# Lamp_Logic_Board_Combo.net
KiCad netlist of a schematic drawn in EAGLE
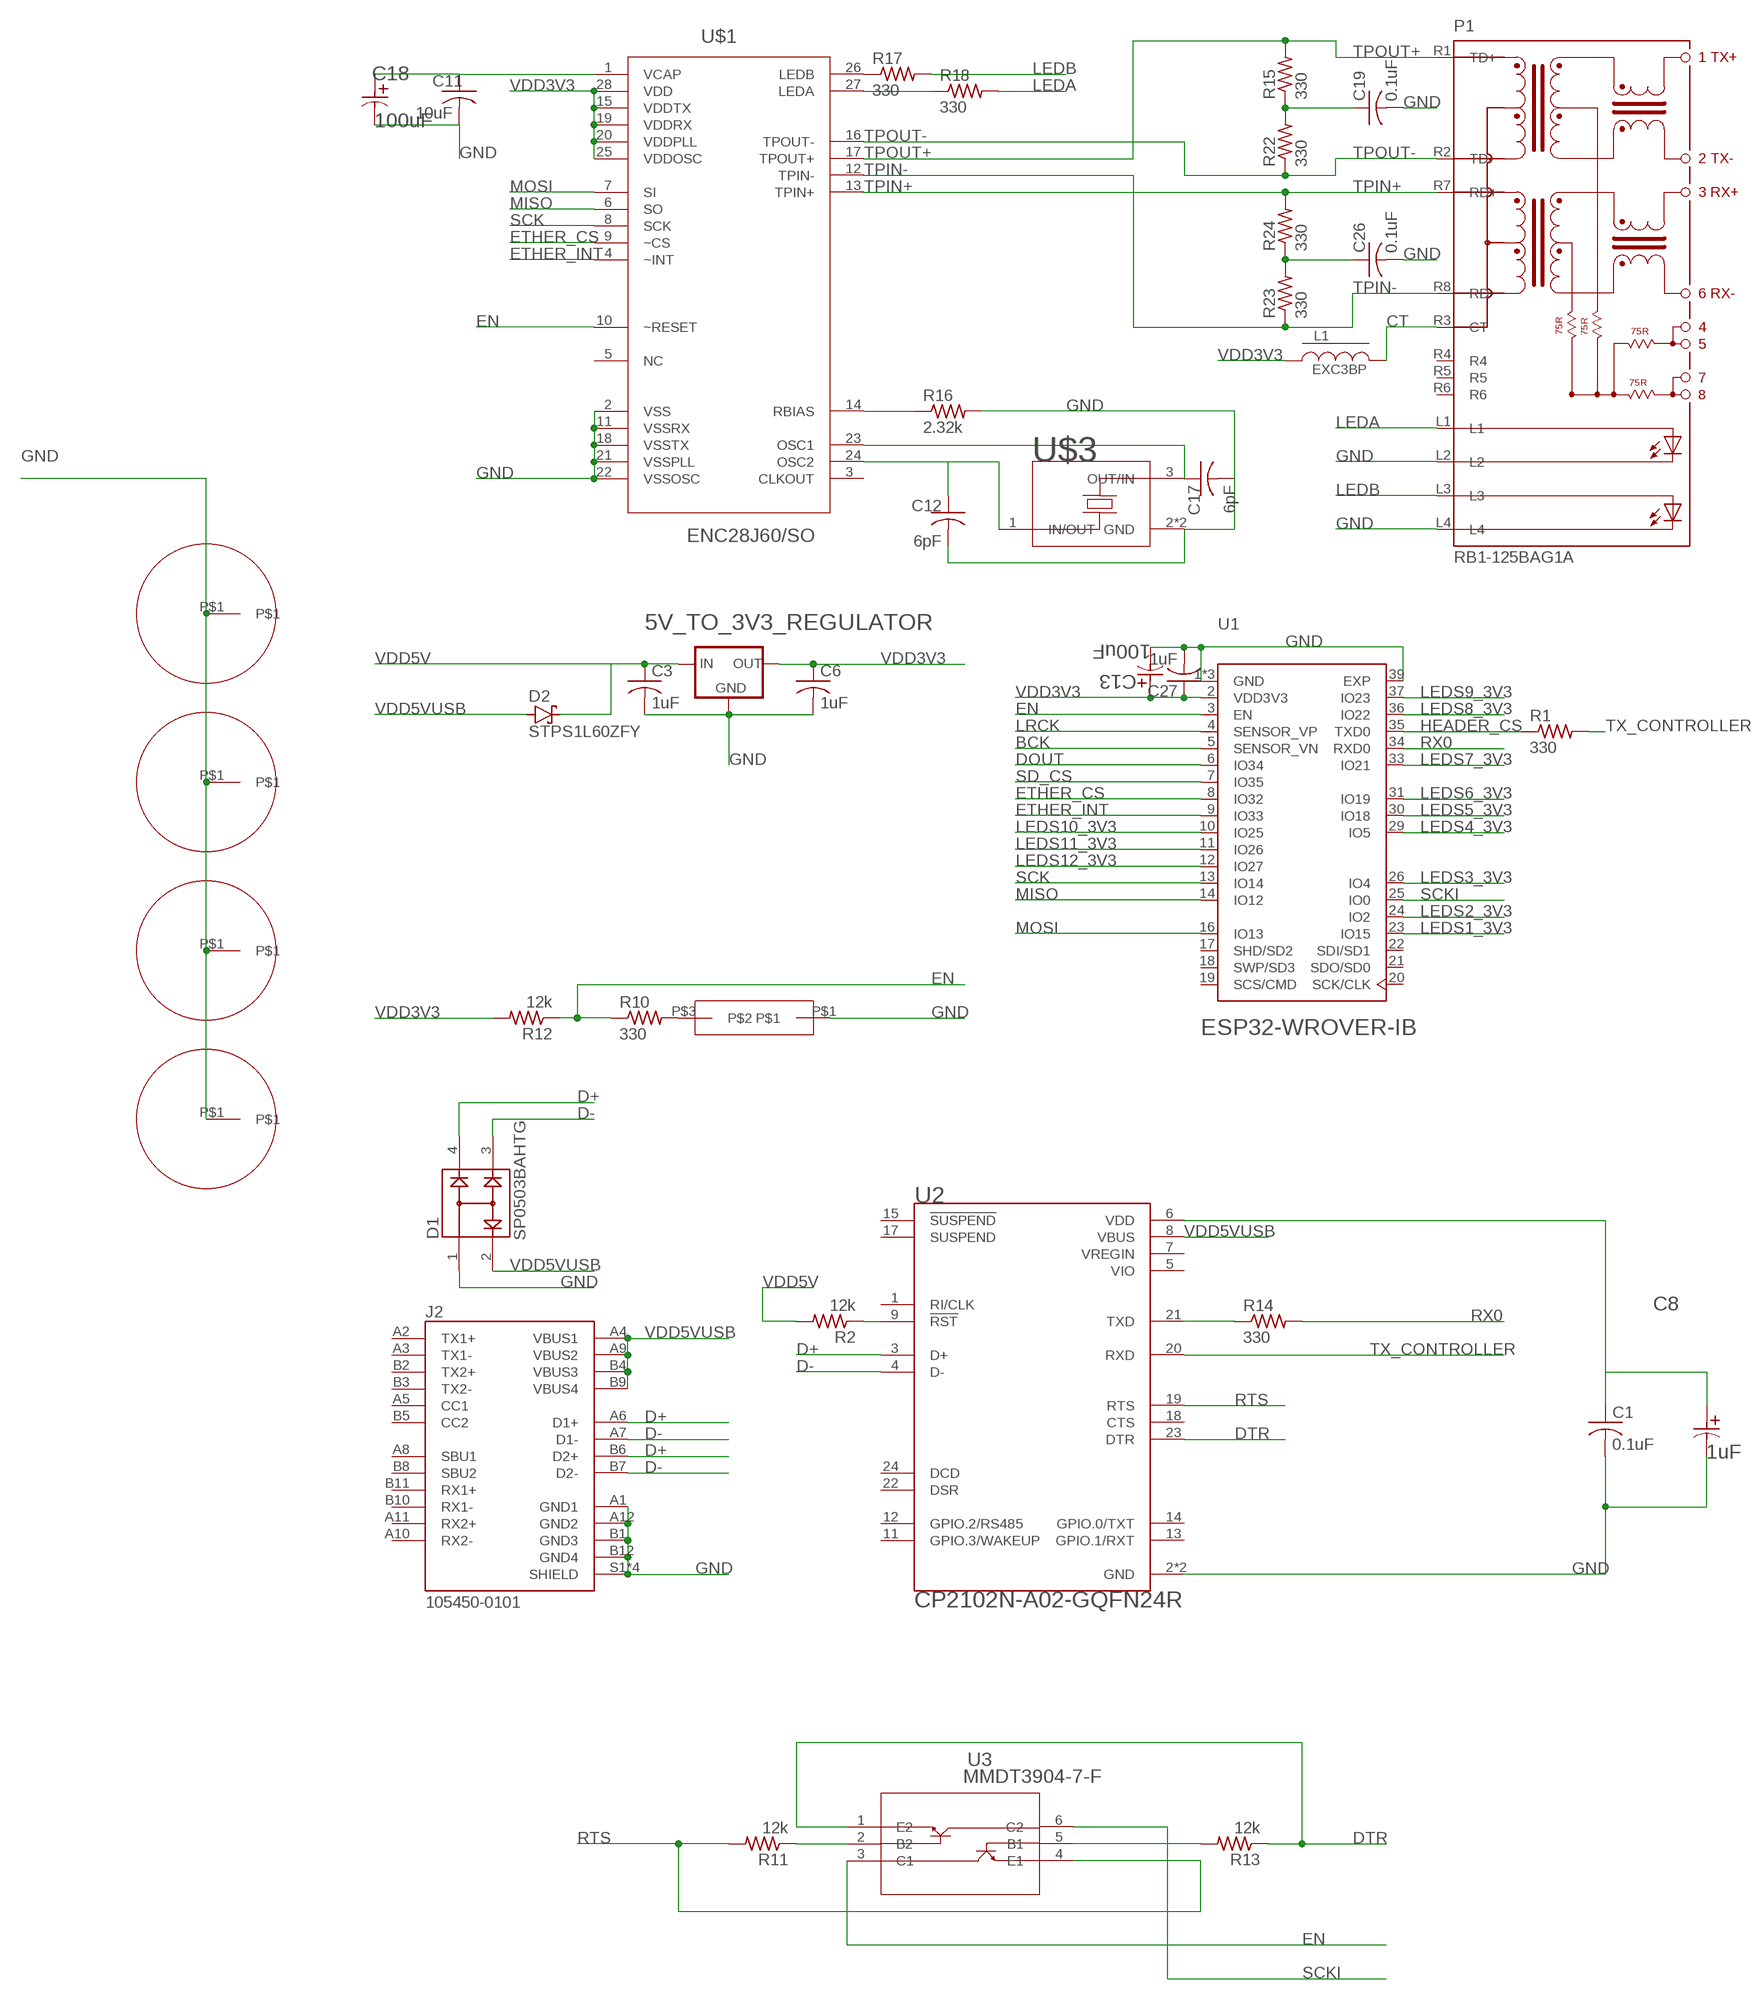
[diagram p0: schematic, sheet 1, part 1 of 2]
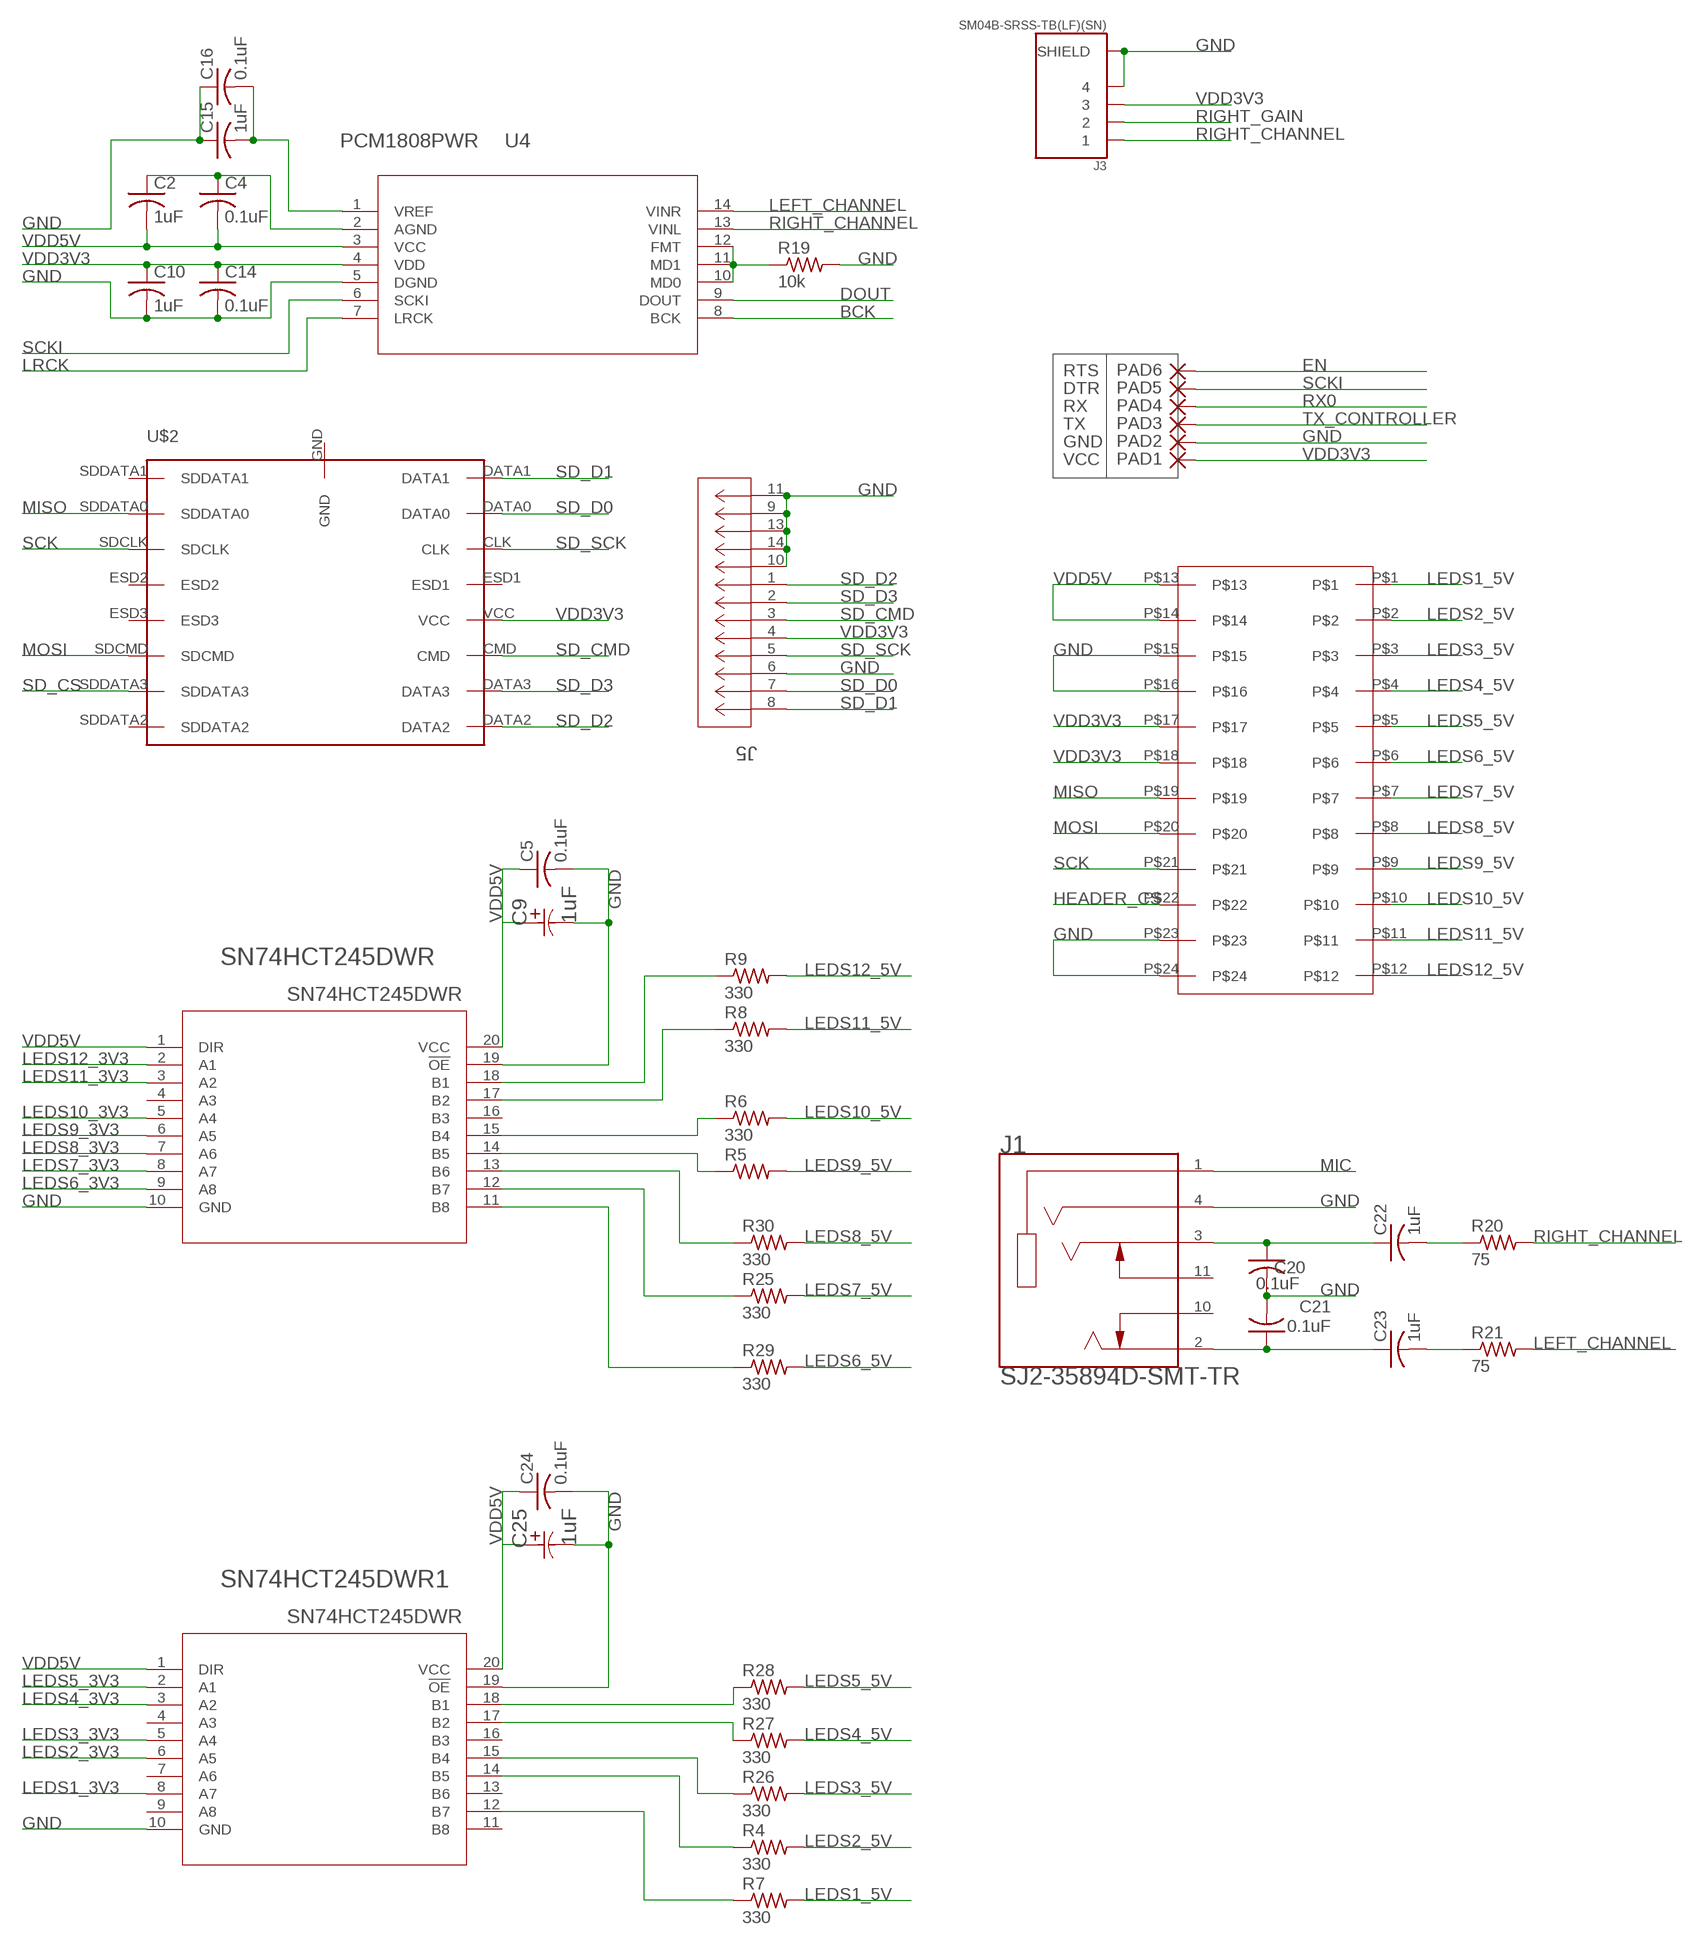
[diagram p1: schematic, sheet 1, part 2 of 2]
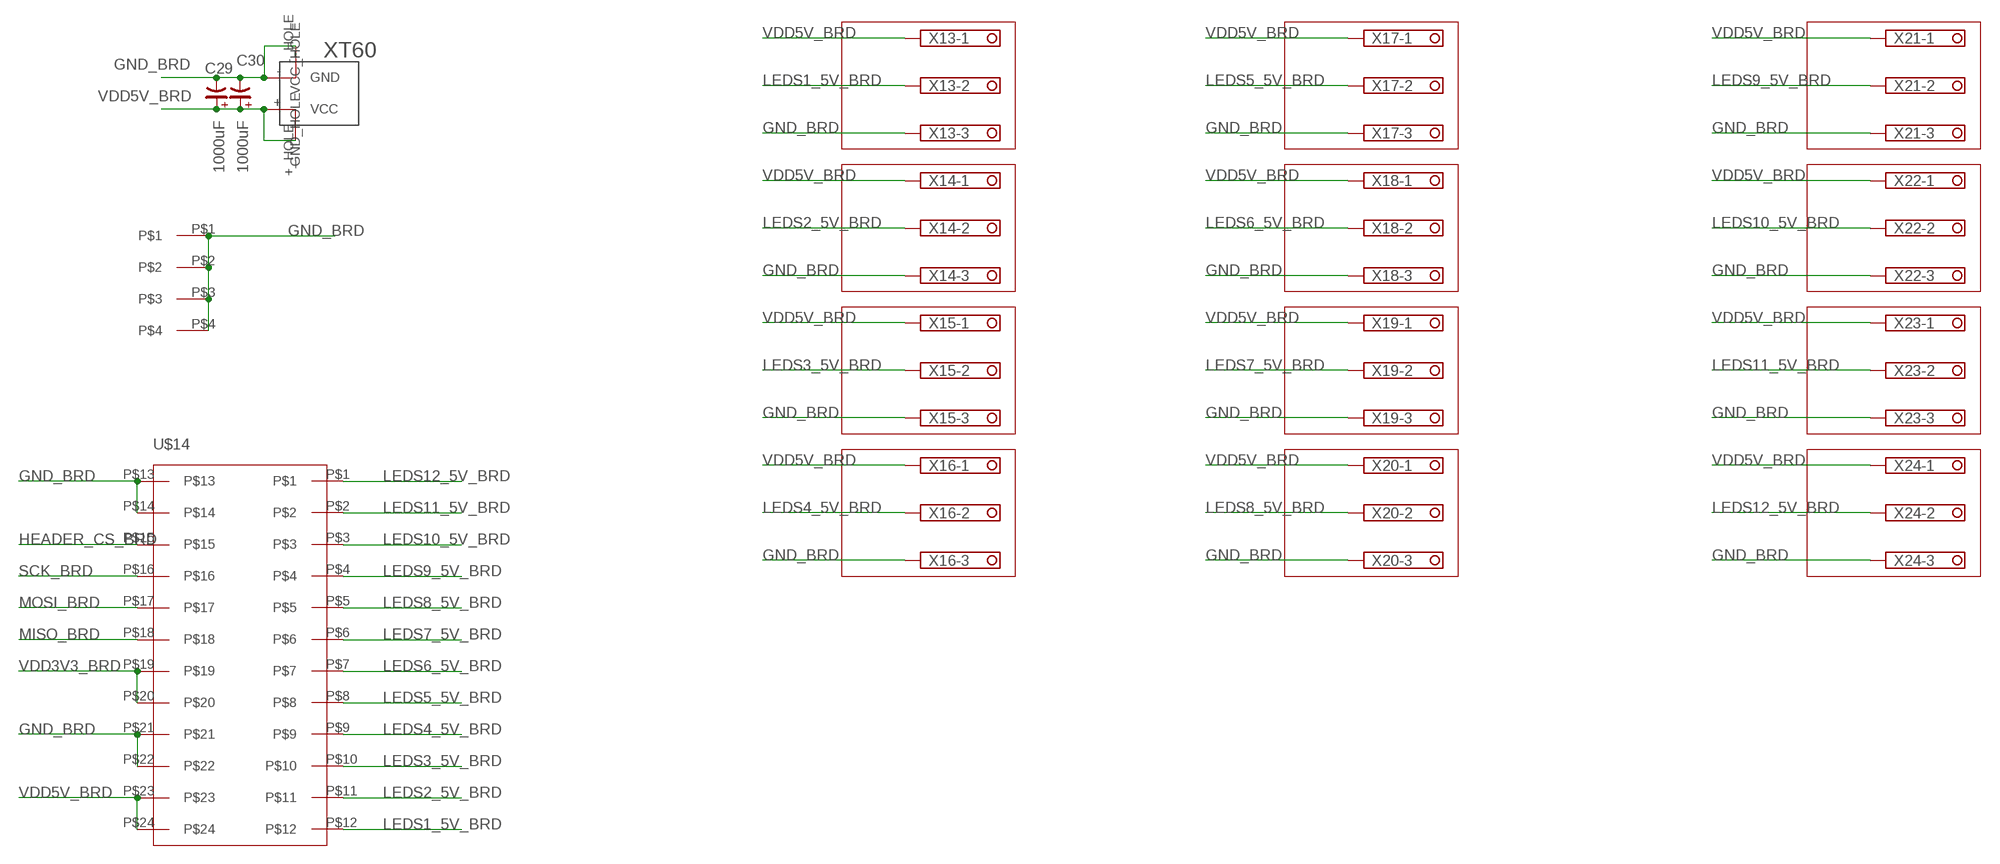
[diagram p2: schematic, sheet 2]

(export (version "E")
  (design (tool "Eeschema 10.0.6"))
  (components
    (comp (ref "5V_TO_3V3_REGULATOR")
      (value "LM1117MP-1.8")
      (footprint "eagle-import:SOT223")
      (fields (field (name "MF") "Texas Instruments"))
      (libsource (lib "eagle-import") (part "LM1117?-MP1.8"))
    )
    (comp (ref "C1")
      (value "0.1uF")
      (footprint "eagle-import:C0402")
      (libsource (lib "eagle-import") (part "resistor_348_C-USC0402"))
    )
    (comp (ref "C2")
      (value "1uF")
      (footprint "eagle-import:C0402")
      (libsource (lib "eagle-import") (part "resistor_348_C-USC0402"))
    )
    (comp (ref "C3")
      (value "1uF")
      (footprint "eagle-import:C0402")
      (libsource (lib "eagle-import") (part "resistor_348_C-USC0402"))
    )
    (comp (ref "C4")
      (value "0.1uF")
      (footprint "eagle-import:C0402")
      (libsource (lib "eagle-import") (part "resistor_348_C-USC0402"))
    )
    (comp (ref "C5")
      (value "0.1uF")
      (footprint "eagle-import:C0402")
      (libsource (lib "eagle-import") (part "C-USC0402"))
    )
    (comp (ref "C6")
      (value "1uF")
      (footprint "eagle-import:C0402")
      (libsource (lib "eagle-import") (part "resistor_348_C-USC0402"))
    )
    (comp (ref "C8")
      (value "1uF")
      (footprint "eagle-import:CAP_EEFC_B")
      (fields (field (name "MANUFACTURER_PART_NUMBER") "EEEFC1V1R0R"))
      (libsource (lib "eagle-import") (part "EEEFC1V1R0R"))
    )
    (comp (ref "C9")
      (value "1uF")
      (footprint "eagle-import:CAP_EEFC_B")
      (fields (field (name "MANUFACTURER_PART_NUMBER") "EEEFC1V1R0R"))
      (libsource (lib "eagle-import") (part "EEEFC1V1R0R"))
    )
    (comp (ref "C10")
      (value "1uF")
      (footprint "eagle-import:C0402")
      (libsource (lib "eagle-import") (part "resistor_348_C-USC0402"))
    )
    (comp (ref "C11")
      (value "10uF")
      (footprint "eagle-import:C0402")
      (libsource (lib "eagle-import") (part "resistor_348_C-USC0402"))
    )
    (comp (ref "C12")
      (value "6pF")
      (footprint "eagle-import:C0402")
      (libsource (lib "eagle-import") (part "resistor_348_C-USC0402"))
    )
    (comp (ref "C13")
      (value "100uF")
      (footprint "eagle-import:CAP_EEFC_B")
      (fields (field (name "MANUFACTURER_PART_NUMBER") "EEEFC1V1R0R"))
      (libsource (lib "eagle-import") (part "EEEFC1V1R0R"))
    )
    (comp (ref "C14")
      (value "0.1uF")
      (footprint "eagle-import:C0402")
      (libsource (lib "eagle-import") (part "resistor_348_C-USC0402"))
    )
    (comp (ref "C15")
      (value "1uF")
      (footprint "eagle-import:C0402")
      (libsource (lib "eagle-import") (part "resistor_348_C-USC0402"))
    )
    (comp (ref "C16")
      (value "0.1uF")
      (footprint "eagle-import:C0402")
      (libsource (lib "eagle-import") (part "resistor_348_C-USC0402"))
    )
    (comp (ref "C17")
      (value "6pF")
      (footprint "eagle-import:C0402")
      (libsource (lib "eagle-import") (part "resistor_348_C-USC0402"))
    )
    (comp (ref "C18")
      (value "100uF")
      (footprint "eagle-import:CAP_EEFC_B")
      (fields (field (name "MANUFACTURER_PART_NUMBER") "EEEFC1V1R0R"))
      (libsource (lib "eagle-import") (part "EEEFC1V1R0R"))
    )
    (comp (ref "C19")
      (value "0.1uF")
      (footprint "eagle-import:C0402")
      (libsource (lib "eagle-import") (part "resistor_348_C-USC0402"))
    )
    (comp (ref "C20")
      (value "0.1uF")
      (footprint "eagle-import:C0402")
      (libsource (lib "eagle-import") (part "C-USC0402"))
    )
    (comp (ref "C21")
      (value "0.1uF")
      (footprint "eagle-import:C0402")
      (libsource (lib "eagle-import") (part "C-USC0402"))
    )
    (comp (ref "C22")
      (value "1uF")
      (footprint "eagle-import:C0402")
      (libsource (lib "eagle-import") (part "resistor_348_C-USC0402"))
    )
    (comp (ref "C23")
      (value "1uF")
      (footprint "eagle-import:C0402")
      (libsource (lib "eagle-import") (part "resistor_348_C-USC0402"))
    )
    (comp (ref "C24")
      (value "0.1uF")
      (footprint "eagle-import:C0402")
      (libsource (lib "eagle-import") (part "C-USC0402"))
    )
    (comp (ref "C25")
      (value "1uF")
      (footprint "eagle-import:CAP_EEFC_B")
      (fields (field (name "MANUFACTURER_PART_NUMBER") "EEEFC1V1R0R"))
      (libsource (lib "eagle-import") (part "EEEFC1V1R0R"))
    )
    (comp (ref "C26")
      (value "0.1uF")
      (footprint "eagle-import:C0402")
      (libsource (lib "eagle-import") (part "resistor_348_C-USC0402"))
    )
    (comp (ref "C27")
      (value "1uF")
      (footprint "eagle-import:C0402")
      (libsource (lib "eagle-import") (part "resistor_348_C-USC0402"))
    )
    (comp (ref "D1")
      (value "SP0503BAHTG")
      (footprint "eagle-import:SOT143")
      (fields (field (name "DIGI-KEY_PART_NUMBER") "F2715CT-ND") (field (name "MF") "Littelfuse Inc."))
      (libsource (lib "eagle-import") (part "SP0503BAHTG"))
    )
    (comp (ref "D2")
      (value "STPS1L60ZFY")
      (footprint "eagle-import:SOD-123")
      (fields
        (field (name "DIGIKEY_PART_NUMBER") "MBR0520LT1GOSTR-ND")
        (field (name "MANUFACTURER") "ON Semiconductor")
        (field (name "MPN") "MBR0520LT1G")
        (field (name "CREATED_BY") "PCBLayout.com")
      )
      (libsource (lib "eagle-import") (part "MBR0520LT1G"))
    )
    (comp (ref "J1")
      (value "SJ2-35894D-SMT-TR")
      (footprint "eagle-import:CUI_SJ2-35894D-SMT-TR")
      (fields (field (name "DIGI-KEY_PART_NUMBER") "CP-SJ2-35894D-SMT-CT-ND") (field (name "MF") "CUI Inc."))
      (libsource (lib "eagle-import") (part "SJ2-35894D-SMT-TR"))
    )
    (comp (ref "J2")
      (value "105450-0101")
      (footprint "eagle-import:MOLEX_105450-0101")
      (fields
        (field (name "DIGI-KEY_PART_NUMBER") "WM12856CT-ND")
        (field (name "MF") "Molex")
        (field (name "MP") "1054500101")
      )
      (libsource (lib "eagle-import") (part "105450-0101"))
    )
    (comp (ref "J3")
      (value "SM04B-SRSS-TB(LF)(SN)")
      (footprint "eagle-import:JST_SM04B-SRSS-TB(LF)(SN)")
      (fields (field (name "MF") "JST Sales") (field (name "MP") "SM04B-SRSS-TB_LF__SN_"))
      (libsource (lib "eagle-import") (part "SM04B-SRSS-TB(LF)(SN)"))
    )
    (comp (ref "J5")
      (value "LLC")
      (footprint "eagle-import:CON00218_8")
      (libsource (lib "eagle-import") (part "LLC"))
    )
    (comp (ref "L1")
      (value "EXC3BP")
      (footprint "eagle-import:L0603")
      (libsource (lib "eagle-import") (part "EXC3BP"))
    )
    (comp (ref "P1")
      (value "RB1-125BAG1A")
      (footprint "eagle-import:WIZNET_RB1-125BAG1A")
      (fields (field (name "MF") "WIZnet"))
      (libsource (lib "eagle-import") (part "RB1-125BAG1A"))
    )
    (comp (ref "PAD1")
      (value "VCC")
      (footprint "eagle-import:SMD1,27-2,54")
      (libsource (lib "eagle-import") (part "WIREPADSMD1,27-254"))
    )
    (comp (ref "PAD2")
      (value "GND")
      (footprint "eagle-import:SMD1,27-2,54")
      (libsource (lib "eagle-import") (part "WIREPADSMD1,27-254"))
    )
    (comp (ref "PAD3")
      (value "TX")
      (footprint "eagle-import:SMD1,27-2,54")
      (libsource (lib "eagle-import") (part "WIREPADSMD1,27-254"))
    )
    (comp (ref "PAD4")
      (value "RX")
      (footprint "eagle-import:SMD1,27-2,54")
      (libsource (lib "eagle-import") (part "WIREPADSMD1,27-254"))
    )
    (comp (ref "PAD5")
      (value "DTR")
      (footprint "eagle-import:SMD1,27-2,54")
      (libsource (lib "eagle-import") (part "WIREPADSMD1,27-254"))
    )
    (comp (ref "PAD6")
      (value "RTS")
      (footprint "eagle-import:SMD1,27-2,54")
      (libsource (lib "eagle-import") (part "WIREPADSMD1,27-254"))
    )
    (comp (ref "R1")
      (value "330")
      (footprint "eagle-import:RES_0603")
      (fields
        (field (name "DIGIKEY_PART_NUMBER") "311-0.0GRTR-ND")
        (field (name "MANUFACTURER") "Yageo")
        (field (name "MPN") "RC0603JR-070RL")
        (field (name "CREATED_BY") "PCBLayout.com")
      )
      (libsource (lib "eagle-import") (part "RC0603JR-070RL"))
    )
    (comp (ref "R2")
      (value "12k")
      (footprint "eagle-import:RES_0603")
      (fields
        (field (name "DIGIKEY_PART_NUMBER") "311-0.0GRTR-ND")
        (field (name "MANUFACTURER") "Yageo")
        (field (name "MPN") "RC0603JR-070RL")
        (field (name "CREATED_BY") "PCBLayout.com")
      )
      (libsource (lib "eagle-import") (part "RC0603JR-070RL"))
    )
    (comp (ref "R4")
      (value "330")
      (footprint "eagle-import:RES_0603")
      (fields
        (field (name "DIGIKEY_PART_NUMBER") "311-0.0GRTR-ND")
        (field (name "MANUFACTURER") "Yageo")
        (field (name "MPN") "RC0603JR-070RL")
        (field (name "CREATED_BY") "PCBLayout.com")
      )
      (libsource (lib "eagle-import") (part "RC0603JR-070RL"))
    )
    (comp (ref "R5")
      (value "330")
      (footprint "eagle-import:RES_0603")
      (fields
        (field (name "DIGIKEY_PART_NUMBER") "311-0.0GRTR-ND")
        (field (name "MANUFACTURER") "Yageo")
        (field (name "MPN") "RC0603JR-070RL")
        (field (name "CREATED_BY") "PCBLayout.com")
      )
      (libsource (lib "eagle-import") (part "RC0603JR-070RL"))
    )
    (comp (ref "R6")
      (value "330")
      (footprint "eagle-import:RES_0603")
      (fields
        (field (name "DIGIKEY_PART_NUMBER") "311-0.0GRTR-ND")
        (field (name "MANUFACTURER") "Yageo")
        (field (name "MPN") "RC0603JR-070RL")
        (field (name "CREATED_BY") "PCBLayout.com")
      )
      (libsource (lib "eagle-import") (part "RC0603JR-070RL"))
    )
    (comp (ref "R7")
      (value "330")
      (footprint "eagle-import:RES_0603")
      (fields
        (field (name "DIGIKEY_PART_NUMBER") "311-0.0GRTR-ND")
        (field (name "MANUFACTURER") "Yageo")
        (field (name "MPN") "RC0603JR-070RL")
        (field (name "CREATED_BY") "PCBLayout.com")
      )
      (libsource (lib "eagle-import") (part "RC0603JR-070RL"))
    )
    (comp (ref "R8")
      (value "330")
      (footprint "eagle-import:RES_0603")
      (fields
        (field (name "DIGIKEY_PART_NUMBER") "311-0.0GRTR-ND")
        (field (name "MANUFACTURER") "Yageo")
        (field (name "MPN") "RC0603JR-070RL")
        (field (name "CREATED_BY") "PCBLayout.com")
      )
      (libsource (lib "eagle-import") (part "RC0603JR-070RL"))
    )
    (comp (ref "R9")
      (value "330")
      (footprint "eagle-import:RES_0603")
      (fields
        (field (name "DIGIKEY_PART_NUMBER") "311-0.0GRTR-ND")
        (field (name "MANUFACTURER") "Yageo")
        (field (name "MPN") "RC0603JR-070RL")
        (field (name "CREATED_BY") "PCBLayout.com")
      )
      (libsource (lib "eagle-import") (part "RC0603JR-070RL"))
    )
    (comp (ref "R10")
      (value "330")
      (footprint "eagle-import:RES_0603")
      (fields
        (field (name "DIGIKEY_PART_NUMBER") "311-0.0GRTR-ND")
        (field (name "MANUFACTURER") "Yageo")
        (field (name "MPN") "RC0603JR-070RL")
        (field (name "CREATED_BY") "PCBLayout.com")
      )
      (libsource (lib "eagle-import") (part "RC0603JR-070RL"))
    )
    (comp (ref "R11")
      (value "12k")
      (footprint "eagle-import:RES_0603")
      (fields
        (field (name "DIGIKEY_PART_NUMBER") "311-0.0GRTR-ND")
        (field (name "MANUFACTURER") "Yageo")
        (field (name "MPN") "RC0603JR-070RL")
        (field (name "CREATED_BY") "PCBLayout.com")
      )
      (libsource (lib "eagle-import") (part "RC0603JR-070RL"))
    )
    (comp (ref "R12")
      (value "12k")
      (footprint "eagle-import:RES_0603")
      (fields
        (field (name "DIGIKEY_PART_NUMBER") "311-0.0GRTR-ND")
        (field (name "MANUFACTURER") "Yageo")
        (field (name "MPN") "RC0603JR-070RL")
        (field (name "CREATED_BY") "PCBLayout.com")
      )
      (libsource (lib "eagle-import") (part "RC0603JR-070RL"))
    )
    (comp (ref "R13")
      (value "12k")
      (footprint "eagle-import:RES_0603")
      (fields
        (field (name "DIGIKEY_PART_NUMBER") "311-0.0GRTR-ND")
        (field (name "MANUFACTURER") "Yageo")
        (field (name "MPN") "RC0603JR-070RL")
        (field (name "CREATED_BY") "PCBLayout.com")
      )
      (libsource (lib "eagle-import") (part "RC0603JR-070RL"))
    )
    (comp (ref "R14")
      (value "330")
      (footprint "eagle-import:RES_0603")
      (fields
        (field (name "DIGIKEY_PART_NUMBER") "311-0.0GRTR-ND")
        (field (name "MANUFACTURER") "Yageo")
        (field (name "MPN") "RC0603JR-070RL")
        (field (name "CREATED_BY") "PCBLayout.com")
      )
      (libsource (lib "eagle-import") (part "RC0603JR-070RL"))
    )
    (comp (ref "R15")
      (value "330")
      (footprint "eagle-import:RES_0603")
      (fields
        (field (name "DIGIKEY_PART_NUMBER") "311-0.0GRTR-ND")
        (field (name "MANUFACTURER") "Yageo")
        (field (name "MPN") "RC0603JR-070RL")
        (field (name "CREATED_BY") "PCBLayout.com")
      )
      (libsource (lib "eagle-import") (part "RC0603JR-070RL"))
    )
    (comp (ref "R16")
      (value "2.32k")
      (footprint "eagle-import:R1206")
      (libsource (lib "eagle-import") (part "R-US_R1206"))
    )
    (comp (ref "R17")
      (value "330")
      (footprint "eagle-import:RES_0603")
      (fields
        (field (name "DIGIKEY_PART_NUMBER") "311-0.0GRTR-ND")
        (field (name "MANUFACTURER") "Yageo")
        (field (name "MPN") "RC0603JR-070RL")
        (field (name "CREATED_BY") "PCBLayout.com")
      )
      (libsource (lib "eagle-import") (part "RC0603JR-070RL"))
    )
    (comp (ref "R18")
      (value "330")
      (footprint "eagle-import:RES_0603")
      (fields
        (field (name "DIGIKEY_PART_NUMBER") "311-0.0GRTR-ND")
        (field (name "MANUFACTURER") "Yageo")
        (field (name "MPN") "RC0603JR-070RL")
        (field (name "CREATED_BY") "PCBLayout.com")
      )
      (libsource (lib "eagle-import") (part "RC0603JR-070RL"))
    )
    (comp (ref "R19")
      (value "10k")
      (footprint "eagle-import:R1206")
      (libsource (lib "eagle-import") (part "R-US_R1206"))
    )
    (comp (ref "R20")
      (value "75")
      (footprint "eagle-import:R1206")
      (libsource (lib "eagle-import") (part "R-US_R1206"))
    )
    (comp (ref "R21")
      (value "75")
      (footprint "eagle-import:R1206")
      (libsource (lib "eagle-import") (part "R-US_R1206"))
    )
    (comp (ref "R22")
      (value "330")
      (footprint "eagle-import:RES_0603")
      (fields
        (field (name "DIGIKEY_PART_NUMBER") "311-0.0GRTR-ND")
        (field (name "MANUFACTURER") "Yageo")
        (field (name "MPN") "RC0603JR-070RL")
        (field (name "CREATED_BY") "PCBLayout.com")
      )
      (libsource (lib "eagle-import") (part "RC0603JR-070RL"))
    )
    (comp (ref "R23")
      (value "330")
      (footprint "eagle-import:RES_0603")
      (fields
        (field (name "DIGIKEY_PART_NUMBER") "311-0.0GRTR-ND")
        (field (name "MANUFACTURER") "Yageo")
        (field (name "MPN") "RC0603JR-070RL")
        (field (name "CREATED_BY") "PCBLayout.com")
      )
      (libsource (lib "eagle-import") (part "RC0603JR-070RL"))
    )
    (comp (ref "R24")
      (value "330")
      (footprint "eagle-import:RES_0603")
      (fields
        (field (name "DIGIKEY_PART_NUMBER") "311-0.0GRTR-ND")
        (field (name "MANUFACTURER") "Yageo")
        (field (name "MPN") "RC0603JR-070RL")
        (field (name "CREATED_BY") "PCBLayout.com")
      )
      (libsource (lib "eagle-import") (part "RC0603JR-070RL"))
    )
    (comp (ref "R25")
      (value "330")
      (footprint "eagle-import:RES_0603")
      (fields
        (field (name "DIGIKEY_PART_NUMBER") "311-0.0GRTR-ND")
        (field (name "MANUFACTURER") "Yageo")
        (field (name "MPN") "RC0603JR-070RL")
        (field (name "CREATED_BY") "PCBLayout.com")
      )
      (libsource (lib "eagle-import") (part "RC0603JR-070RL"))
    )
    (comp (ref "R26")
      (value "330")
      (footprint "eagle-import:RES_0603")
      (fields
        (field (name "DIGIKEY_PART_NUMBER") "311-0.0GRTR-ND")
        (field (name "MANUFACTURER") "Yageo")
        (field (name "MPN") "RC0603JR-070RL")
        (field (name "CREATED_BY") "PCBLayout.com")
      )
      (libsource (lib "eagle-import") (part "RC0603JR-070RL"))
    )
    (comp (ref "R27")
      (value "330")
      (footprint "eagle-import:RES_0603")
      (fields
        (field (name "DIGIKEY_PART_NUMBER") "311-0.0GRTR-ND")
        (field (name "MANUFACTURER") "Yageo")
        (field (name "MPN") "RC0603JR-070RL")
        (field (name "CREATED_BY") "PCBLayout.com")
      )
      (libsource (lib "eagle-import") (part "RC0603JR-070RL"))
    )
    (comp (ref "R28")
      (value "330")
      (footprint "eagle-import:RES_0603")
      (fields
        (field (name "DIGIKEY_PART_NUMBER") "311-0.0GRTR-ND")
        (field (name "MANUFACTURER") "Yageo")
        (field (name "MPN") "RC0603JR-070RL")
        (field (name "CREATED_BY") "PCBLayout.com")
      )
      (libsource (lib "eagle-import") (part "RC0603JR-070RL"))
    )
    (comp (ref "R29")
      (value "330")
      (footprint "eagle-import:RES_0603")
      (fields
        (field (name "DIGIKEY_PART_NUMBER") "311-0.0GRTR-ND")
        (field (name "MANUFACTURER") "Yageo")
        (field (name "MPN") "RC0603JR-070RL")
        (field (name "CREATED_BY") "PCBLayout.com")
      )
      (libsource (lib "eagle-import") (part "RC0603JR-070RL"))
    )
    (comp (ref "R30")
      (value "330")
      (footprint "eagle-import:RES_0603")
      (fields
        (field (name "DIGIKEY_PART_NUMBER") "311-0.0GRTR-ND")
        (field (name "MANUFACTURER") "Yageo")
        (field (name "MPN") "RC0603JR-070RL")
        (field (name "CREATED_BY") "PCBLayout.com")
      )
      (libsource (lib "eagle-import") (part "RC0603JR-070RL"))
    )
    (comp (ref "SN74HCT245DWR")
      (value "SN74HCT245DWR")
      (footprint "eagle-import:DW20")
      (libsource (lib "eagle-import") (part "SN74HCT245DWR"))
    )
    (comp (ref "SN74HCT245DWR1")
      (value "SN74HCT245DWR")
      (footprint "eagle-import:DW20")
      (libsource (lib "eagle-import") (part "SN74HCT245DWR"))
    )
    (comp (ref "U$1")
      (value "ENC28J60/SO")
      (footprint "eagle-import:SOIC127P1034X264-28N")
      (fields
        (field (name "DIGI-KEY_PART_NUMBER") "ENC28J60/SS-ND")
        (field (name "MF") "Microchip")
        (field (name "MP") "ENC28J60/SS")
      )
      (libsource (lib "eagle-import") (part "ENC28J60/SO"))
    )
    (comp (ref "U$2")
      (value "CM1624-08DE")
      (footprint "eagle-import:CM1624-08DE")
      (libsource (lib "eagle-import") (part "CM1624-08DE"))
    )
    (comp (ref "U$3")
      (value "ECS-250-10-37B-CTN-TR")
      (footprint "eagle-import:ECS-250-10-37B-CTN-TR")
      (libsource (lib "eagle-import") (part "ECS-250-10-37B-CTN-TR"))
    )
    (comp (ref "U$4")
      (value "QUICKFIT_RISER_THING")
      (footprint "eagle-import:QUICKFIT_RISER_THING")
      (libsource (lib "eagle-import") (part "QUICKFIT_RISER_THING"))
    )
    (comp (ref "U$5")
      (value "QUICKFIT_RISER_THING")
      (footprint "eagle-import:QUICKFIT_RISER_THING")
      (libsource (lib "eagle-import") (part "QUICKFIT_RISER_THING"))
    )
    (comp (ref "U$6")
      (value "QUICKFIT_RISER_THING")
      (footprint "eagle-import:QUICKFIT_RISER_THING")
      (libsource (lib "eagle-import") (part "QUICKFIT_RISER_THING"))
    )
    (comp (ref "U$7")
      (value "TL1014BF160QG")
      (footprint "eagle-import:TL1014BF160QG")
      (libsource (lib "eagle-import") (part "TL1014BF160QG"))
    )
    (comp (ref "U$8")
      (value "QUICKFIT_RISER_THING")
      (footprint "eagle-import:QUICKFIT_RISER_THING")
      (libsource (lib "eagle-import") (part "QUICKFIT_RISER_THING"))
    )
    (comp (ref "U$9")
      (value "MY_HEADER")
      (footprint "eagle-import:MY_HEADER")
      (libsource (lib "eagle-import") (part "MY_HEADER"))
    )
    (comp (ref "U1")
      (value "ESP32-WROVER-IB")
      (footprint "eagle-import:XCVR_ESP32-WROVER-I")
      (fields (field (name "MF") "Espressif Systems") (field (name "MP") "ESP32-WROVER-I"))
      (libsource (lib "eagle-import") (part "ESP32-WROVER-I"))
    )
    (comp (ref "U2")
      (value "CP2102N-A02-GQFN24R")
      (footprint "eagle-import:SILABS_CP2102N-A02-GQFN24R")
      (libsource (lib "eagle-import") (part "CP2102N-A02-GQFN24R"))
    )
    (comp (ref "U3")
      (value "MMDT3904-7-F")
      (footprint "eagle-import:SOT-363")
      (fields (field (name "MANUFACTURER_PART_NUMBER") "MMDT39047F"))
      (libsource (lib "eagle-import") (part "MMDT3904-7-F"))
    )
    (comp (ref "U4")
      (value "PCM1808PWR")
      (footprint "eagle-import:PW14")
      (libsource (lib "eagle-import") (part "PCM1808PWR"))
    )
    (comp (ref "C29")
      (value "1000uF")
      (footprint "eagle-import:CSV-G")
      (libsource (lib "eagle-import") (part "CP_SV-G"))
    )
    (comp (ref "C30")
      (value "1000uF")
      (footprint "eagle-import:CSV-G")
      (libsource (lib "eagle-import") (part "CP_SV-G"))
    )
    (comp (ref "U$13,U$14")
      (value "POWERBOARD_TEMPLATEPOWERBOARD_TEMPLATE")
      (footprint "eagle-import:4,PIECE")
      (libsource (lib "eagle-import") (part "POWERBOARD_TEMPLATEPOWERBOARD_TEMPLATE"))
    )
    (comp (ref "U$14")
      (value "MY_HEADER")
      (footprint "eagle-import:MY_HEADER")
      (libsource (lib "eagle-import") (part "MY_HEADER"))
    )
    (comp (ref "U$15")
      (value "XT60")
      (footprint "eagle-import:XT60")
      (libsource (lib "eagle-import") (part "XT60"))
    )
    (comp (ref "X13")
      (value "TERMINAL-BLOCK-3.5MM-3-PIN-LONG-PAD")
      (footprint "eagle-import:TERMINAL-BLOCK-3-PIN-3.5MM-LONG-PAD")
      (libsource (lib "eagle-import") (part "TERMINAL-BLOCK-3.5MM-3-PIN-LONG-PAD"))
    )
    (comp (ref "X14")
      (value "TERMINAL-BLOCK-3.5MM-3-PIN-LONG-PAD")
      (footprint "eagle-import:TERMINAL-BLOCK-3-PIN-3.5MM-LONG-PAD")
      (libsource (lib "eagle-import") (part "TERMINAL-BLOCK-3.5MM-3-PIN-LONG-PAD"))
    )
    (comp (ref "X15")
      (value "TERMINAL-BLOCK-3.5MM-3-PIN-LONG-PAD")
      (footprint "eagle-import:TERMINAL-BLOCK-3-PIN-3.5MM-LONG-PAD")
      (libsource (lib "eagle-import") (part "TERMINAL-BLOCK-3.5MM-3-PIN-LONG-PAD"))
    )
    (comp (ref "X16")
      (value "TERMINAL-BLOCK-3.5MM-3-PIN-LONG-PAD")
      (footprint "eagle-import:TERMINAL-BLOCK-3-PIN-3.5MM-LONG-PAD")
      (libsource (lib "eagle-import") (part "TERMINAL-BLOCK-3.5MM-3-PIN-LONG-PAD"))
    )
    (comp (ref "X17")
      (value "TERMINAL-BLOCK-3.5MM-3-PIN-LONG-PAD")
      (footprint "eagle-import:TERMINAL-BLOCK-3-PIN-3.5MM-LONG-PAD")
      (libsource (lib "eagle-import") (part "TERMINAL-BLOCK-3.5MM-3-PIN-LONG-PAD"))
    )
    (comp (ref "X18")
      (value "TERMINAL-BLOCK-3.5MM-3-PIN-LONG-PAD")
      (footprint "eagle-import:TERMINAL-BLOCK-3-PIN-3.5MM-LONG-PAD")
      (libsource (lib "eagle-import") (part "TERMINAL-BLOCK-3.5MM-3-PIN-LONG-PAD"))
    )
    (comp (ref "X19")
      (value "TERMINAL-BLOCK-3.5MM-3-PIN-LONG-PAD")
      (footprint "eagle-import:TERMINAL-BLOCK-3-PIN-3.5MM-LONG-PAD")
      (libsource (lib "eagle-import") (part "TERMINAL-BLOCK-3.5MM-3-PIN-LONG-PAD"))
    )
    (comp (ref "X20")
      (value "TERMINAL-BLOCK-3.5MM-3-PIN-LONG-PAD")
      (footprint "eagle-import:TERMINAL-BLOCK-3-PIN-3.5MM-LONG-PAD")
      (libsource (lib "eagle-import") (part "TERMINAL-BLOCK-3.5MM-3-PIN-LONG-PAD"))
    )
    (comp (ref "X21")
      (value "TERMINAL-BLOCK-3.5MM-3-PIN-LONG-PAD")
      (footprint "eagle-import:TERMINAL-BLOCK-3-PIN-3.5MM-LONG-PAD")
      (libsource (lib "eagle-import") (part "TERMINAL-BLOCK-3.5MM-3-PIN-LONG-PAD"))
    )
    (comp (ref "X22")
      (value "TERMINAL-BLOCK-3.5MM-3-PIN-LONG-PAD")
      (footprint "eagle-import:TERMINAL-BLOCK-3-PIN-3.5MM-LONG-PAD")
      (libsource (lib "eagle-import") (part "TERMINAL-BLOCK-3.5MM-3-PIN-LONG-PAD"))
    )
    (comp (ref "X23")
      (value "TERMINAL-BLOCK-3.5MM-3-PIN-LONG-PAD")
      (footprint "eagle-import:TERMINAL-BLOCK-3-PIN-3.5MM-LONG-PAD")
      (libsource (lib "eagle-import") (part "TERMINAL-BLOCK-3.5MM-3-PIN-LONG-PAD"))
    )
    (comp (ref "X24")
      (value "TERMINAL-BLOCK-3.5MM-3-PIN-LONG-PAD")
      (footprint "eagle-import:TERMINAL-BLOCK-3-PIN-3.5MM-LONG-PAD")
      (libsource (lib "eagle-import") (part "TERMINAL-BLOCK-3.5MM-3-PIN-LONG-PAD"))
    )
  )
  (nets
    (net (code "1") (name "BCK") (class "Default")
      (node (ref "U1") (pin "5") (pinfunction "SENSOR_VN_5") (pintype "input"))
      (node (ref "U4") (pin "8") (pinfunction "BCK_8") (pintype "bidirectional"))
    )
    (net (code "2") (name "CT") (class "Default")
      (node (ref "L1") (pin "2") (pinfunction "2_2") (pintype "passive"))
      (node (ref "P1") (pin "R3") (pinfunction "CT_R3") (pintype "input"))
    )
    (net (code "3") (name "D+") (class "Default")
      (node (ref "D1") (pin "4") (pinfunction "4_4") (pintype "passive"))
      (node (ref "J2") (pin "A6") (pinfunction "D1+_A6") (pintype "passive"))
      (node (ref "J2") (pin "B6") (pinfunction "D2+_B6") (pintype "passive"))
      (node (ref "U2") (pin "3") (pinfunction "D+_3") (pintype "bidirectional"))
    )
    (net (code "4") (name "D-") (class "Default")
      (node (ref "D1") (pin "3") (pinfunction "3_3") (pintype "passive"))
      (node (ref "J2") (pin "A7") (pinfunction "D1-_A7") (pintype "passive"))
      (node (ref "J2") (pin "B7") (pinfunction "D2-_B7") (pintype "passive"))
      (node (ref "U2") (pin "4") (pinfunction "D-_4") (pintype "bidirectional"))
    )
    (net (code "5") (name "DOUT") (class "Default")
      (node (ref "U1") (pin "6") (pinfunction "IO34_6") (pintype "input"))
      (node (ref "U4") (pin "9") (pinfunction "DOUT_9") (pintype "output"))
    )
    (net (code "6") (name "DTR") (class "Default")
      (node (ref "R13") (pin "1") (pinfunction "1_1") (pintype "passive"))
      (node (ref "U2") (pin "23") (pinfunction "DTR_23") (pintype "bidirectional"))
      (node (ref "U3") (pin "1") (pinfunction "E2_1") (pintype "passive"))
    )
    (net (code "7") (name "EN") (class "Default")
      (node (ref "PAD6") (pin "1") (pinfunction "P_1") (pintype "passive"))
      (node (ref "R10") (pin "1") (pinfunction "1_1") (pintype "passive"))
      (node (ref "R12") (pin "1") (pinfunction "1_1") (pintype "passive"))
      (node (ref "U$1") (pin "10") (pinfunction "~{RESET}_10") (pintype "input"))
      (node (ref "U1") (pin "3") (pinfunction "EN_3") (pintype "input"))
      (node (ref "U3") (pin "3") (pinfunction "C1_3") (pintype "passive"))
    )
    (net (code "8") (name "ETHER_CS") (class "Default")
      (node (ref "U$1") (pin "9") (pinfunction "~{CS}_9") (pintype "input"))
      (node (ref "U1") (pin "8") (pinfunction "IO32_8") (pintype "bidirectional"))
    )
    (net (code "9") (name "ETHER_INT") (class "Default")
      (node (ref "U$1") (pin "4") (pinfunction "~{INT}_4") (pintype "output"))
      (node (ref "U1") (pin "9") (pinfunction "IO33_9") (pintype "bidirectional"))
    )
    (net (code "10") (name "GND") (class "Default")
      (node (ref "5V_TO_3V3_REGULATOR") (pin "1") (pinfunction "GND_1") (pintype "input"))
      (node (ref "C1") (pin "2") (pinfunction "2_2") (pintype "passive"))
      (node (ref "C10") (pin "2") (pinfunction "2_2") (pintype "passive"))
      (node (ref "C11") (pin "2") (pinfunction "2_2") (pintype "passive"))
      (node (ref "C12") (pin "2") (pinfunction "2_2") (pintype "passive"))
      (node (ref "C13") (pin "2") (pinfunction "2_2") (pintype "passive"))
      (node (ref "C14") (pin "2") (pinfunction "2_2") (pintype "passive"))
      (node (ref "C15") (pin "1") (pinfunction "1_1") (pintype "passive"))
      (node (ref "C16") (pin "1") (pinfunction "1_1") (pintype "passive"))
      (node (ref "C17") (pin "2") (pinfunction "2_2") (pintype "passive"))
      (node (ref "C18") (pin "2") (pinfunction "2_2") (pintype "passive"))
      (node (ref "C19") (pin "2") (pinfunction "2_2") (pintype "passive"))
      (node (ref "C20") (pin "2") (pinfunction "2_2") (pintype "passive"))
      (node (ref "C21") (pin "2") (pinfunction "2_2") (pintype "passive"))
      (node (ref "C24") (pin "2") (pinfunction "2_2") (pintype "passive"))
      (node (ref "C25") (pin "2") (pinfunction "2_2") (pintype "passive"))
      (node (ref "C26") (pin "2") (pinfunction "2_2") (pintype "passive"))
      (node (ref "C27") (pin "2") (pinfunction "2_2") (pintype "passive"))
      (node (ref "C3") (pin "2") (pinfunction "2_2") (pintype "passive"))
      (node (ref "C5") (pin "2") (pinfunction "2_2") (pintype "passive"))
      (node (ref "C6") (pin "2") (pinfunction "2_2") (pintype "passive"))
      (node (ref "C8") (pin "2") (pinfunction "2_2") (pintype "passive"))
      (node (ref "C9") (pin "2") (pinfunction "2_2") (pintype "passive"))
      (node (ref "D1") (pin "1") (pinfunction "1_1") (pintype "passive"))
      (node (ref "J1") (pin "4") (pinfunction "RING2_4") (pintype "passive"))
      (node (ref "J2") (pin "A1") (pinfunction "GND1_A1") (pintype "passive"))
      (node (ref "J2") (pin "A12") (pinfunction "GND2_A12") (pintype "passive"))
      (node (ref "J2") (pin "B1") (pinfunction "GND3_B1") (pintype "passive"))
      (node (ref "J2") (pin "B12") (pinfunction "GND4_B12") (pintype "passive"))
      (node (ref "J2") (pin "S1") (pinfunction "SHIELD_S1") (pintype "passive"))
      (node (ref "J2") (pin "S2") (pinfunction "SHIELD_S2") (pintype "passive"))
      (node (ref "J2") (pin "S3") (pinfunction "SHIELD_S3") (pintype "passive"))
      (node (ref "J2") (pin "S4") (pinfunction "SHIELD_S4") (pintype "passive"))
      (node (ref "J3") (pin "4") (pinfunction "4_4") (pintype "passive"))
      (node (ref "J3") (pin "S1") (pinfunction "SHIELD_S1") (pintype "passive"))
      (node (ref "J3") (pin "S2") (pinfunction "SHIELD_S2") (pintype "passive"))
      (node (ref "J5") (pin "10") (pinfunction "10_10") (pintype "passive"))
      (node (ref "J5") (pin "11") (pinfunction "11_11") (pintype "passive"))
      (node (ref "J5") (pin "13") (pinfunction "13_13") (pintype "passive"))
      (node (ref "J5") (pin "14") (pinfunction "14_14") (pintype "passive"))
      (node (ref "J5") (pin "6") (pinfunction "6_6") (pintype "passive"))
      (node (ref "J5") (pin "9") (pinfunction "9_9") (pintype "passive"))
      (node (ref "P1") (pin "L2") (pinfunction "L2_L2") (pintype "passive"))
      (node (ref "P1") (pin "L4") (pinfunction "L4_L4") (pintype "passive"))
      (node (ref "PAD2") (pin "1") (pinfunction "P_1") (pintype "passive"))
      (node (ref "R16") (pin "2") (pinfunction "2_2") (pintype "passive"))
      (node (ref "R19") (pin "2") (pinfunction "2_2") (pintype "passive"))
      (node (ref "SN74HCT245DWR") (pin "10") (pinfunction "GND_10") (pintype "power_in"))
      (node (ref "SN74HCT245DWR") (pin "19") (pinfunction "~{OE}_19") (pintype "input"))
      (node (ref "SN74HCT245DWR1") (pin "10") (pinfunction "GND_10") (pintype "power_in"))
      (node (ref "SN74HCT245DWR1") (pin "19") (pinfunction "~{OE}_19") (pintype "input"))
      (node (ref "U$1") (pin "11") (pinfunction "VSSRX_11") (pintype "power_in"))
      (node (ref "U$1") (pin "18") (pinfunction "VSSTX_18") (pintype "power_in"))
      (node (ref "U$1") (pin "2") (pinfunction "VSS_2") (pintype "power_in"))
      (node (ref "U$1") (pin "21") (pinfunction "VSSPLL_21") (pintype "power_in"))
      (node (ref "U$1") (pin "22") (pinfunction "VSSOSC_22") (pintype "power_in"))
      (node (ref "U$3") (pin "2") (pinfunction "GND_2") (pintype "bidirectional"))
      (node (ref "U$3") (pin "4") (pinfunction "GND_4") (pintype "bidirectional"))
      (node (ref "U$4") (pin "P$1") (pinfunction "P$1_P$1") (pintype "bidirectional"))
      (node (ref "U$5") (pin "P$1") (pinfunction "P$1_P$1") (pintype "bidirectional"))
      (node (ref "U$6") (pin "P$1") (pinfunction "P$1_P$1") (pintype "bidirectional"))
      (node (ref "U$7") (pin "P$1") (pinfunction "P$1_P$1") (pintype "bidirectional"))
      (node (ref "U$8") (pin "P$1") (pinfunction "P$1_P$1") (pintype "bidirectional"))
      (node (ref "U$9") (pin "P$15") (pinfunction "P$15_P$15") (pintype "bidirectional"))
      (node (ref "U$9") (pin "P$16") (pinfunction "P$16_P$16") (pintype "bidirectional"))
      (node (ref "U$9") (pin "P$23") (pinfunction "P$23_P$23") (pintype "bidirectional"))
      (node (ref "U$9") (pin "P$24") (pinfunction "P$24_P$24") (pintype "bidirectional"))
      (node (ref "U1") (pin "1") (pinfunction "GND_1") (pintype "power_in"))
      (node (ref "U1") (pin "15") (pinfunction "GND_15") (pintype "power_in"))
      (node (ref "U1") (pin "38") (pinfunction "GND_38") (pintype "power_in"))
      (node (ref "U1") (pin "39") (pinfunction "EXP_39") (pintype "power_in"))
      (node (ref "U2") (pin "2") (pinfunction "GND_2") (pintype "power_in"))
      (node (ref "U2") (pin "25") (pinfunction "GND_25") (pintype "power_in"))
      (node (ref "U4") (pin "5") (pinfunction "DGND_5") (pintype "power_in"))
    )
    (net (code "11") (name "GND_BRD") (class "Default")
      (node (ref "C29") (pin "-") (pinfunction "-_-") (pintype "passive"))
      (node (ref "C30") (pin "-") (pinfunction "-_-") (pintype "passive"))
      (node (ref "U$13,U$14") (pin "P$1") (pinfunction "P$1_P$1") (pintype "bidirectional"))
      (node (ref "U$13,U$14") (pin "P$2") (pinfunction "P$2_P$2") (pintype "bidirectional"))
      (node (ref "U$13,U$14") (pin "P$3") (pinfunction "P$3_P$3") (pintype "bidirectional"))
      (node (ref "U$13,U$14") (pin "P$4") (pinfunction "P$4_P$4") (pintype "bidirectional"))
      (node (ref "U$14") (pin "P$13") (pinfunction "P$13_P$13") (pintype "bidirectional"))
      (node (ref "U$14") (pin "P$14") (pinfunction "P$14_P$14") (pintype "bidirectional"))
      (node (ref "U$14") (pin "P$21") (pinfunction "P$21_P$21") (pintype "bidirectional"))
      (node (ref "U$14") (pin "P$22") (pinfunction "P$22_P$22") (pintype "bidirectional"))
      (node (ref "U$15") (pin "-") (pinfunction "GND_-") (pintype "bidirectional"))
      (node (ref "U$15") (pin "-_HOLE") (pinfunction "GND_HOLE_-_HOLE") (pintype "bidirectional"))
      (node (ref "X13") (pin "3") (pinfunction "K_3") (pintype "passive"))
      (node (ref "X14") (pin "3") (pinfunction "K_3") (pintype "passive"))
      (node (ref "X15") (pin "3") (pinfunction "K_3") (pintype "passive"))
      (node (ref "X16") (pin "3") (pinfunction "K_3") (pintype "passive"))
      (node (ref "X17") (pin "3") (pinfunction "K_3") (pintype "passive"))
      (node (ref "X18") (pin "3") (pinfunction "K_3") (pintype "passive"))
      (node (ref "X19") (pin "3") (pinfunction "K_3") (pintype "passive"))
      (node (ref "X20") (pin "3") (pinfunction "K_3") (pintype "passive"))
      (node (ref "X21") (pin "3") (pinfunction "K_3") (pintype "passive"))
      (node (ref "X22") (pin "3") (pinfunction "K_3") (pintype "passive"))
      (node (ref "X23") (pin "3") (pinfunction "K_3") (pintype "passive"))
      (node (ref "X24") (pin "3") (pinfunction "K_3") (pintype "passive"))
    )
    (net (code "12") (name "HEADER_CS") (class "Default")
      (node (ref "R1") (pin "1") (pinfunction "1_1") (pintype "passive"))
      (node (ref "U$9") (pin "P$22") (pinfunction "P$22_P$22") (pintype "bidirectional"))
      (node (ref "U1") (pin "35") (pinfunction "TXD0_35") (pintype "bidirectional"))
    )
    (net (code "13") (name "HEADER_CS_BRD") (class "Default")
      (node (ref "U$14") (pin "P$15") (pinfunction "P$15_P$15") (pintype "bidirectional"))
    )
    (net (code "14") (name "LEDA") (class "Default")
      (node (ref "P1") (pin "L1") (pinfunction "L1_L1") (pintype "passive"))
      (node (ref "R18") (pin "2") (pinfunction "2_2") (pintype "passive"))
    )
    (net (code "15") (name "LEDB") (class "Default")
      (node (ref "P1") (pin "L3") (pinfunction "L3_L3") (pintype "passive"))
      (node (ref "R17") (pin "2") (pinfunction "2_2") (pintype "passive"))
    )
    (net (code "16") (name "LEDS1_3V3") (class "Default")
      (node (ref "SN74HCT245DWR1") (pin "8") (pinfunction "A7_8") (pintype "bidirectional"))
      (node (ref "U1") (pin "23") (pinfunction "IO15_23") (pintype "bidirectional"))
    )
    (net (code "17") (name "LEDS1_5V") (class "Default")
      (node (ref "R7") (pin "2") (pinfunction "2_2") (pintype "passive"))
      (node (ref "U$9") (pin "P$1") (pinfunction "P$1_P$1") (pintype "bidirectional"))
    )
    (net (code "18") (name "LEDS1_5V_BRD") (class "Default")
      (node (ref "U$14") (pin "P$12") (pinfunction "P$12_P$12") (pintype "bidirectional"))
      (node (ref "X13") (pin "2") (pinfunction "K_2") (pintype "passive"))
    )
    (net (code "19") (name "LEDS2_3V3") (class "Default")
      (node (ref "SN74HCT245DWR1") (pin "6") (pinfunction "A5_6") (pintype "bidirectional"))
      (node (ref "U1") (pin "24") (pinfunction "IO2_24") (pintype "bidirectional"))
    )
    (net (code "20") (name "LEDS2_5V") (class "Default")
      (node (ref "R4") (pin "2") (pinfunction "2_2") (pintype "passive"))
      (node (ref "U$9") (pin "P$2") (pinfunction "P$2_P$2") (pintype "bidirectional"))
    )
    (net (code "21") (name "LEDS2_5V_BRD") (class "Default")
      (node (ref "U$14") (pin "P$11") (pinfunction "P$11_P$11") (pintype "bidirectional"))
      (node (ref "X14") (pin "2") (pinfunction "K_2") (pintype "passive"))
    )
    (net (code "22") (name "LEDS3_3V3") (class "Default")
      (node (ref "SN74HCT245DWR1") (pin "5") (pinfunction "A4_5") (pintype "bidirectional"))
      (node (ref "U1") (pin "26") (pinfunction "IO4_26") (pintype "bidirectional"))
    )
    (net (code "23") (name "LEDS3_5V") (class "Default")
      (node (ref "R26") (pin "2") (pinfunction "2_2") (pintype "passive"))
      (node (ref "U$9") (pin "P$3") (pinfunction "P$3_P$3") (pintype "bidirectional"))
    )
    (net (code "24") (name "LEDS3_5V_BRD") (class "Default")
      (node (ref "U$14") (pin "P$10") (pinfunction "P$10_P$10") (pintype "bidirectional"))
      (node (ref "X15") (pin "2") (pinfunction "K_2") (pintype "passive"))
    )
    (net (code "25") (name "LEDS4_3V3") (class "Default")
      (node (ref "SN74HCT245DWR1") (pin "3") (pinfunction "A2_3") (pintype "bidirectional"))
      (node (ref "U1") (pin "29") (pinfunction "IO5_29") (pintype "bidirectional"))
    )
    (net (code "26") (name "LEDS4_5V") (class "Default")
      (node (ref "R27") (pin "2") (pinfunction "2_2") (pintype "passive"))
      (node (ref "U$9") (pin "P$4") (pinfunction "P$4_P$4") (pintype "bidirectional"))
    )
    (net (code "27") (name "LEDS4_5V_BRD") (class "Default")
      (node (ref "U$14") (pin "P$9") (pinfunction "P$9_P$9") (pintype "bidirectional"))
      (node (ref "X16") (pin "2") (pinfunction "K_2") (pintype "passive"))
    )
    (net (code "28") (name "LEDS5_3V3") (class "Default")
      (node (ref "SN74HCT245DWR1") (pin "2") (pinfunction "A1_2") (pintype "bidirectional"))
      (node (ref "U1") (pin "30") (pinfunction "IO18_30") (pintype "bidirectional"))
    )
    (net (code "29") (name "LEDS5_5V") (class "Default")
      (node (ref "R28") (pin "2") (pinfunction "2_2") (pintype "passive"))
      (node (ref "U$9") (pin "P$5") (pinfunction "P$5_P$5") (pintype "bidirectional"))
    )
    (net (code "30") (name "LEDS5_5V_BRD") (class "Default")
      (node (ref "U$14") (pin "P$8") (pinfunction "P$8_P$8") (pintype "bidirectional"))
      (node (ref "X17") (pin "2") (pinfunction "K_2") (pintype "passive"))
    )
    (net (code "31") (name "LEDS6_3V3") (class "Default")
      (node (ref "SN74HCT245DWR") (pin "9") (pinfunction "A8_9") (pintype "bidirectional"))
      (node (ref "U1") (pin "31") (pinfunction "IO19_31") (pintype "bidirectional"))
    )
    (net (code "32") (name "LEDS6_5V") (class "Default")
      (node (ref "R29") (pin "2") (pinfunction "2_2") (pintype "passive"))
      (node (ref "U$9") (pin "P$6") (pinfunction "P$6_P$6") (pintype "bidirectional"))
    )
    (net (code "33") (name "LEDS6_5V_BRD") (class "Default")
      (node (ref "U$14") (pin "P$7") (pinfunction "P$7_P$7") (pintype "bidirectional"))
      (node (ref "X18") (pin "2") (pinfunction "K_2") (pintype "passive"))
    )
    (net (code "34") (name "LEDS7_3V3") (class "Default")
      (node (ref "SN74HCT245DWR") (pin "8") (pinfunction "A7_8") (pintype "bidirectional"))
      (node (ref "U1") (pin "33") (pinfunction "IO21_33") (pintype "bidirectional"))
    )
    (net (code "35") (name "LEDS7_5V") (class "Default")
      (node (ref "R25") (pin "2") (pinfunction "2_2") (pintype "passive"))
      (node (ref "U$9") (pin "P$7") (pinfunction "P$7_P$7") (pintype "bidirectional"))
    )
    (net (code "36") (name "LEDS7_5V_BRD") (class "Default")
      (node (ref "U$14") (pin "P$6") (pinfunction "P$6_P$6") (pintype "bidirectional"))
      (node (ref "X19") (pin "2") (pinfunction "K_2") (pintype "passive"))
    )
    (net (code "37") (name "LEDS8_3V3") (class "Default")
      (node (ref "SN74HCT245DWR") (pin "7") (pinfunction "A6_7") (pintype "bidirectional"))
      (node (ref "U1") (pin "36") (pinfunction "IO22_36") (pintype "bidirectional"))
    )
    (net (code "38") (name "LEDS8_5V") (class "Default")
      (node (ref "R30") (pin "2") (pinfunction "2_2") (pintype "passive"))
      (node (ref "U$9") (pin "P$8") (pinfunction "P$8_P$8") (pintype "bidirectional"))
    )
    (net (code "39") (name "LEDS8_5V_BRD") (class "Default")
      (node (ref "U$14") (pin "P$5") (pinfunction "P$5_P$5") (pintype "bidirectional"))
      (node (ref "X20") (pin "2") (pinfunction "K_2") (pintype "passive"))
    )
    (net (code "40") (name "LEDS9_3V3") (class "Default")
      (node (ref "SN74HCT245DWR") (pin "6") (pinfunction "A5_6") (pintype "bidirectional"))
      (node (ref "U1") (pin "37") (pinfunction "IO23_37") (pintype "bidirectional"))
    )
    (net (code "41") (name "LEDS9_5V") (class "Default")
      (node (ref "R5") (pin "2") (pinfunction "2_2") (pintype "passive"))
      (node (ref "U$9") (pin "P$9") (pinfunction "P$9_P$9") (pintype "bidirectional"))
    )
    (net (code "42") (name "LEDS9_5V_BRD") (class "Default")
      (node (ref "U$14") (pin "P$4") (pinfunction "P$4_P$4") (pintype "bidirectional"))
      (node (ref "X21") (pin "2") (pinfunction "K_2") (pintype "passive"))
    )
    (net (code "43") (name "LEDS10_3V3") (class "Default")
      (node (ref "SN74HCT245DWR") (pin "5") (pinfunction "A4_5") (pintype "bidirectional"))
      (node (ref "U1") (pin "10") (pinfunction "IO25_10") (pintype "bidirectional"))
    )
    (net (code "44") (name "LEDS10_5V") (class "Default")
      (node (ref "R6") (pin "2") (pinfunction "2_2") (pintype "passive"))
      (node (ref "U$9") (pin "P$10") (pinfunction "P$10_P$10") (pintype "bidirectional"))
    )
    (net (code "45") (name "LEDS10_5V_BRD") (class "Default")
      (node (ref "U$14") (pin "P$3") (pinfunction "P$3_P$3") (pintype "bidirectional"))
      (node (ref "X22") (pin "2") (pinfunction "K_2") (pintype "passive"))
    )
    (net (code "46") (name "LEDS11_3V3") (class "Default")
      (node (ref "SN74HCT245DWR") (pin "3") (pinfunction "A2_3") (pintype "bidirectional"))
      (node (ref "U1") (pin "11") (pinfunction "IO26_11") (pintype "bidirectional"))
    )
    (net (code "47") (name "LEDS11_5V") (class "Default")
      (node (ref "R8") (pin "2") (pinfunction "2_2") (pintype "passive"))
      (node (ref "U$9") (pin "P$11") (pinfunction "P$11_P$11") (pintype "bidirectional"))
    )
    (net (code "48") (name "LEDS11_5V_BRD") (class "Default")
      (node (ref "U$14") (pin "P$2") (pinfunction "P$2_P$2") (pintype "bidirectional"))
      (node (ref "X23") (pin "2") (pinfunction "K_2") (pintype "passive"))
    )
    (net (code "49") (name "LEDS12_3V3") (class "Default")
      (node (ref "SN74HCT245DWR") (pin "2") (pinfunction "A1_2") (pintype "bidirectional"))
      (node (ref "U1") (pin "12") (pinfunction "IO27_12") (pintype "bidirectional"))
    )
    (net (code "50") (name "LEDS12_5V") (class "Default")
      (node (ref "R9") (pin "2") (pinfunction "2_2") (pintype "passive"))
      (node (ref "U$9") (pin "P$12") (pinfunction "P$12_P$12") (pintype "bidirectional"))
    )
    (net (code "51") (name "LEDS12_5V_BRD") (class "Default")
      (node (ref "U$14") (pin "P$1") (pinfunction "P$1_P$1") (pintype "bidirectional"))
      (node (ref "X24") (pin "2") (pinfunction "K_2") (pintype "passive"))
    )
    (net (code "52") (name "LEFT_CHANNEL") (class "Default")
      (node (ref "R21") (pin "2") (pinfunction "2_2") (pintype "passive"))
      (node (ref "U4") (pin "14") (pinfunction "VINR_14") (pintype "input"))
    )
    (net (code "53") (name "LRCK") (class "Default")
      (node (ref "U1") (pin "4") (pinfunction "SENSOR_VP_4") (pintype "input"))
      (node (ref "U4") (pin "7") (pinfunction "LRCK_7") (pintype "bidirectional"))
    )
    (net (code "54") (name "MIC") (class "Default")
      (node (ref "J1") (pin "1") (pinfunction "SLEEVE_1") (pintype "passive"))
    )
    (net (code "55") (name "MISO") (class "Default")
      (node (ref "U$1") (pin "6") (pinfunction "SO_6") (pintype "output"))
      (node (ref "U$2") (pin "SDDATA0") (pinfunction "SDDATA0_SDDATA0") (pintype "bidirectional"))
      (node (ref "U$9") (pin "P$19") (pinfunction "P$19_P$19") (pintype "bidirectional"))
      (node (ref "U1") (pin "14") (pinfunction "IO12_14") (pintype "bidirectional"))
    )
    (net (code "56") (name "MISO_BRD") (class "Default")
      (node (ref "U$14") (pin "P$18") (pinfunction "P$18_P$18") (pintype "bidirectional"))
    )
    (net (code "57") (name "MOSI") (class "Default")
      (node (ref "U$1") (pin "7") (pinfunction "SI_7") (pintype "input"))
      (node (ref "U$2") (pin "SDCMD") (pinfunction "SDCMD_SDCMD") (pintype "bidirectional"))
      (node (ref "U$9") (pin "P$20") (pinfunction "P$20_P$20") (pintype "bidirectional"))
      (node (ref "U1") (pin "16") (pinfunction "IO13_16") (pintype "bidirectional"))
    )
    (net (code "58") (name "MOSI_BRD") (class "Default")
      (node (ref "U$14") (pin "P$17") (pinfunction "P$17_P$17") (pintype "bidirectional"))
    )
    (net (code "59") (name "Net-(C19-Pad1)") (class "Default")
      (node (ref "C19") (pin "1") (pinfunction "1_1") (pintype "passive"))
      (node (ref "R15") (pin "1") (pinfunction "1_1") (pintype "passive"))
      (node (ref "R22") (pin "2") (pinfunction "2_2") (pintype "passive"))
    )
    (net (code "60") (name "Net-(C22-Pad2)") (class "Default")
      (node (ref "C22") (pin "2") (pinfunction "2_2") (pintype "passive"))
      (node (ref "R20") (pin "1") (pinfunction "1_1") (pintype "passive"))
    )
    (net (code "61") (name "Net-(C23-Pad2)") (class "Default")
      (node (ref "C23") (pin "2") (pinfunction "2_2") (pintype "passive"))
      (node (ref "R21") (pin "1") (pinfunction "1_1") (pintype "passive"))
    )
    (net (code "62") (name "Net-(C26-Pad1)") (class "Default")
      (node (ref "C26") (pin "1") (pinfunction "1_1") (pintype "passive"))
      (node (ref "R23") (pin "2") (pinfunction "2_2") (pintype "passive"))
      (node (ref "R24") (pin "1") (pinfunction "1_1") (pintype "passive"))
    )
    (net (code "63") (name "Net-(J1-RING1)") (class "Default")
      (node (ref "C20") (pin "1") (pinfunction "1_1") (pintype "passive"))
      (node (ref "C22") (pin "1") (pinfunction "1_1") (pintype "passive"))
      (node (ref "J1") (pin "3") (pinfunction "RING1_3") (pintype "passive"))
    )
    (net (code "64") (name "Net-(J1-TIP)") (class "Default")
      (node (ref "C21") (pin "1") (pinfunction "1_1") (pintype "passive"))
      (node (ref "C23") (pin "1") (pinfunction "1_1") (pintype "passive"))
      (node (ref "J1") (pin "2") (pinfunction "TIP_2") (pintype "passive"))
    )
    (net (code "65") (name "Net-(SN74HCT245DWR-B1)") (class "Default")
      (node (ref "R9") (pin "1") (pinfunction "1_1") (pintype "passive"))
      (node (ref "SN74HCT245DWR") (pin "18") (pinfunction "B1_18") (pintype "bidirectional"))
    )
    (net (code "66") (name "Net-(SN74HCT245DWR-B2)") (class "Default")
      (node (ref "R8") (pin "1") (pinfunction "1_1") (pintype "passive"))
      (node (ref "SN74HCT245DWR") (pin "17") (pinfunction "B2_17") (pintype "bidirectional"))
    )
    (net (code "67") (name "Net-(SN74HCT245DWR-B4)") (class "Default")
      (node (ref "R6") (pin "1") (pinfunction "1_1") (pintype "passive"))
      (node (ref "SN74HCT245DWR") (pin "15") (pinfunction "B4_15") (pintype "bidirectional"))
    )
    (net (code "68") (name "Net-(SN74HCT245DWR-B5)") (class "Default")
      (node (ref "R5") (pin "1") (pinfunction "1_1") (pintype "passive"))
      (node (ref "SN74HCT245DWR") (pin "14") (pinfunction "B5_14") (pintype "bidirectional"))
    )
    (net (code "69") (name "Net-(SN74HCT245DWR-B6)") (class "Default")
      (node (ref "R30") (pin "1") (pinfunction "1_1") (pintype "passive"))
      (node (ref "SN74HCT245DWR") (pin "13") (pinfunction "B6_13") (pintype "bidirectional"))
    )
    (net (code "70") (name "Net-(SN74HCT245DWR-B7)") (class "Default")
      (node (ref "R25") (pin "1") (pinfunction "1_1") (pintype "passive"))
      (node (ref "SN74HCT245DWR") (pin "12") (pinfunction "B7_12") (pintype "bidirectional"))
    )
    (net (code "71") (name "Net-(SN74HCT245DWR-B8)") (class "Default")
      (node (ref "R29") (pin "1") (pinfunction "1_1") (pintype "passive"))
      (node (ref "SN74HCT245DWR") (pin "11") (pinfunction "B8_11") (pintype "bidirectional"))
    )
    (net (code "72") (name "Net-(SN74HCT245DWR1-B1)") (class "Default")
      (node (ref "R28") (pin "1") (pinfunction "1_1") (pintype "passive"))
      (node (ref "SN74HCT245DWR1") (pin "18") (pinfunction "B1_18") (pintype "bidirectional"))
    )
    (net (code "73") (name "Net-(SN74HCT245DWR1-B2)") (class "Default")
      (node (ref "R27") (pin "1") (pinfunction "1_1") (pintype "passive"))
      (node (ref "SN74HCT245DWR1") (pin "17") (pinfunction "B2_17") (pintype "bidirectional"))
    )
    (net (code "74") (name "Net-(SN74HCT245DWR1-B4)") (class "Default")
      (node (ref "R26") (pin "1") (pinfunction "1_1") (pintype "passive"))
      (node (ref "SN74HCT245DWR1") (pin "15") (pinfunction "B4_15") (pintype "bidirectional"))
    )
    (net (code "75") (name "Net-(SN74HCT245DWR1-B5)") (class "Default")
      (node (ref "R4") (pin "1") (pinfunction "1_1") (pintype "passive"))
      (node (ref "SN74HCT245DWR1") (pin "14") (pinfunction "B5_14") (pintype "bidirectional"))
    )
    (net (code "76") (name "Net-(SN74HCT245DWR1-B7)") (class "Default")
      (node (ref "R7") (pin "1") (pinfunction "1_1") (pintype "passive"))
      (node (ref "SN74HCT245DWR1") (pin "12") (pinfunction "B7_12") (pintype "bidirectional"))
    )
    (net (code "77") (name "Net-(U$1-LEDA)") (class "Default")
      (node (ref "R18") (pin "1") (pinfunction "1_1") (pintype "passive"))
      (node (ref "U$1") (pin "27") (pinfunction "LEDA_27") (pintype "output"))
    )
    (net (code "78") (name "Net-(U$1-LEDB)") (class "Default")
      (node (ref "R17") (pin "1") (pinfunction "1_1") (pintype "passive"))
      (node (ref "U$1") (pin "26") (pinfunction "LEDB_26") (pintype "output"))
    )
    (net (code "79") (name "Net-(U$1-OSC1)") (class "Default")
      (node (ref "C17") (pin "1") (pinfunction "1_1") (pintype "passive"))
      (node (ref "U$1") (pin "23") (pinfunction "OSC1_23") (pintype "input"))
      (node (ref "U$3") (pin "3") (pinfunction "OUT/IN_3") (pintype "bidirectional"))
    )
    (net (code "80") (name "Net-(U$1-OSC2)") (class "Default")
      (node (ref "C12") (pin "1") (pinfunction "1_1") (pintype "passive"))
      (node (ref "U$1") (pin "24") (pinfunction "OSC2_24") (pintype "output"))
      (node (ref "U$3") (pin "1") (pinfunction "IN/OUT_1") (pintype "bidirectional"))
    )
    (net (code "81") (name "Net-(U$1-RBIAS)") (class "Default")
      (node (ref "R16") (pin "1") (pinfunction "1_1") (pintype "passive"))
      (node (ref "U$1") (pin "14") (pinfunction "RBIAS_14") (pintype "input"))
    )
    (net (code "82") (name "Net-(U$1-VCAP)") (class "Default")
      (node (ref "C11") (pin "1") (pinfunction "1_1") (pintype "passive"))
      (node (ref "C18") (pin "1") (pinfunction "1_1") (pintype "passive"))
      (node (ref "U$1") (pin "1") (pinfunction "VCAP_1") (pintype "input"))
    )
    (net (code "83") (name "Net-(U$7-P$2)") (class "Default")
      (node (ref "R10") (pin "2") (pinfunction "2_2") (pintype "passive"))
      (node (ref "U$7") (pin "P$3") (pinfunction "P$2_P$3") (pintype "bidirectional"))
    )
    (net (code "84") (name "Net-(U2-TXD)") (class "Default")
      (node (ref "R14") (pin "1") (pinfunction "1_1") (pintype "passive"))
      (node (ref "U2") (pin "21") (pinfunction "TXD_21") (pintype "output"))
    )
    (net (code "85") (name "Net-(U2-VDD)") (class "Default")
      (node (ref "C1") (pin "1") (pinfunction "1_1") (pintype "passive"))
      (node (ref "C8") (pin "1") (pinfunction "1_1") (pintype "passive"))
      (node (ref "U2") (pin "6") (pinfunction "VDD_6") (pintype "power_in"))
    )
    (net (code "86") (name "Net-(U2-~{RST})") (class "Default")
      (node (ref "R2") (pin "1") (pinfunction "1_1") (pintype "passive"))
      (node (ref "U2") (pin "9") (pinfunction "~{RST}_9") (pintype "input"))
    )
    (net (code "87") (name "Net-(U3-B1)") (class "Default")
      (node (ref "R13") (pin "2") (pinfunction "2_2") (pintype "passive"))
      (node (ref "U3") (pin "5") (pinfunction "B1_5") (pintype "passive"))
    )
    (net (code "88") (name "Net-(U3-B2)") (class "Default")
      (node (ref "R11") (pin "1") (pinfunction "1_1") (pintype "passive"))
      (node (ref "U3") (pin "2") (pinfunction "B2_2") (pintype "passive"))
    )
    (net (code "89") (name "Net-(U4-AGND)") (class "Default")
      (node (ref "C2") (pin "1") (pinfunction "1_1") (pintype "passive"))
      (node (ref "C4") (pin "1") (pinfunction "1_1") (pintype "passive"))
      (node (ref "U4") (pin "2") (pinfunction "AGND_2") (pintype "power_in"))
    )
    (net (code "90") (name "Net-(U4-FMT)") (class "Default")
      (node (ref "R19") (pin "1") (pinfunction "1_1") (pintype "passive"))
      (node (ref "U4") (pin "10") (pinfunction "MD0_10") (pintype "input"))
      (node (ref "U4") (pin "11") (pinfunction "MD1_11") (pintype "input"))
      (node (ref "U4") (pin "12") (pinfunction "FMT_12") (pintype "input"))
    )
    (net (code "91") (name "Net-(U4-VREF)") (class "Default")
      (node (ref "C15") (pin "2") (pinfunction "2_2") (pintype "passive"))
      (node (ref "C16") (pin "2") (pinfunction "2_2") (pintype "passive"))
      (node (ref "U4") (pin "1") (pinfunction "VREF_1") (pintype "power_in"))
    )
    (net (code "92") (name "RIGHT_CHANNEL") (class "Default")
      (node (ref "J3") (pin "1") (pinfunction "1_1") (pintype "passive"))
      (node (ref "R20") (pin "2") (pinfunction "2_2") (pintype "passive"))
      (node (ref "U4") (pin "13") (pinfunction "VINL_13") (pintype "input"))
    )
    (net (code "93") (name "RIGHT_GAIN") (class "Default")
      (node (ref "J3") (pin "2") (pinfunction "2_2") (pintype "passive"))
    )
    (net (code "94") (name "RTS") (class "Default")
      (node (ref "R11") (pin "2") (pinfunction "2_2") (pintype "passive"))
      (node (ref "U2") (pin "19") (pinfunction "RTS_19") (pintype "output"))
      (node (ref "U3") (pin "4") (pinfunction "E1_4") (pintype "passive"))
    )
    (net (code "95") (name "RX0") (class "Default")
      (node (ref "PAD4") (pin "1") (pinfunction "P_1") (pintype "passive"))
      (node (ref "R14") (pin "2") (pinfunction "2_2") (pintype "passive"))
      (node (ref "U1") (pin "34") (pinfunction "RXD0_34") (pintype "bidirectional"))
    )
    (net (code "96") (name "SCK") (class "Default")
      (node (ref "U$1") (pin "8") (pinfunction "SCK_8") (pintype "input"))
      (node (ref "U$2") (pin "SDCLK") (pinfunction "SDCLK_SDCLK") (pintype "bidirectional"))
      (node (ref "U$9") (pin "P$21") (pinfunction "P$21_P$21") (pintype "bidirectional"))
      (node (ref "U1") (pin "13") (pinfunction "IO14_13") (pintype "bidirectional"))
    )
    (net (code "97") (name "SCKI") (class "Default")
      (node (ref "PAD5") (pin "1") (pinfunction "P_1") (pintype "passive"))
      (node (ref "U1") (pin "25") (pinfunction "IO0_25") (pintype "bidirectional"))
      (node (ref "U3") (pin "6") (pinfunction "C2_6") (pintype "passive"))
      (node (ref "U4") (pin "6") (pinfunction "SCKI_6") (pintype "input"))
    )
    (net (code "98") (name "SCK_BRD") (class "Default")
      (node (ref "U$14") (pin "P$16") (pinfunction "P$16_P$16") (pintype "bidirectional"))
    )
    (net (code "99") (name "SD_CMD") (class "Default")
      (node (ref "J5") (pin "3") (pinfunction "3_3") (pintype "passive"))
      (node (ref "U$2") (pin "CMD") (pinfunction "CMD_CMD") (pintype "bidirectional"))
    )
    (net (code "100") (name "SD_CS") (class "Default")
      (node (ref "U$2") (pin "SDDATA3") (pinfunction "SDDATA3_SDDATA3") (pintype "bidirectional"))
      (node (ref "U1") (pin "7") (pinfunction "IO35_7") (pintype "input"))
    )
    (net (code "101") (name "SD_D0") (class "Default")
      (node (ref "J5") (pin "7") (pinfunction "7_7") (pintype "passive"))
      (node (ref "U$2") (pin "DATA0") (pinfunction "DATA0_DATA0") (pintype "bidirectional"))
    )
    (net (code "102") (name "SD_D1") (class "Default")
      (node (ref "J5") (pin "8") (pinfunction "8_8") (pintype "passive"))
      (node (ref "U$2") (pin "DATA1") (pinfunction "DATA1_DATA1") (pintype "bidirectional"))
    )
    (net (code "103") (name "SD_D2") (class "Default")
      (node (ref "J5") (pin "1") (pinfunction "1_1") (pintype "passive"))
      (node (ref "U$2") (pin "DATA2") (pinfunction "DATA2_DATA2") (pintype "bidirectional"))
    )
    (net (code "104") (name "SD_D3") (class "Default")
      (node (ref "J5") (pin "2") (pinfunction "2_2") (pintype "passive"))
      (node (ref "U$2") (pin "DATA3") (pinfunction "DATA3_DATA3") (pintype "bidirectional"))
    )
    (net (code "105") (name "SD_SCK") (class "Default")
      (node (ref "J5") (pin "5") (pinfunction "5_5") (pintype "passive"))
      (node (ref "U$2") (pin "CLK") (pinfunction "CLK_CLK") (pintype "bidirectional"))
    )
    (net (code "106") (name "TPIN+") (class "Default")
      (node (ref "P1") (pin "R7") (pinfunction "RD+_R7") (pintype "input"))
      (node (ref "R24") (pin "2") (pinfunction "2_2") (pintype "passive"))
      (node (ref "U$1") (pin "13") (pinfunction "TPIN+_13") (pintype "input"))
    )
    (net (code "107") (name "TPIN-") (class "Default")
      (node (ref "P1") (pin "R8") (pinfunction "RD-_R8") (pintype "input"))
      (node (ref "R23") (pin "1") (pinfunction "1_1") (pintype "passive"))
      (node (ref "U$1") (pin "12") (pinfunction "TPIN-_12") (pintype "input"))
    )
    (net (code "108") (name "TPOUT+") (class "Default")
      (node (ref "P1") (pin "R1") (pinfunction "TD+_R1") (pintype "input"))
      (node (ref "R15") (pin "2") (pinfunction "2_2") (pintype "passive"))
      (node (ref "U$1") (pin "17") (pinfunction "TPOUT+_17") (pintype "output"))
    )
    (net (code "109") (name "TPOUT-") (class "Default")
      (node (ref "P1") (pin "R2") (pinfunction "TD-_R2") (pintype "input"))
      (node (ref "R22") (pin "1") (pinfunction "1_1") (pintype "passive"))
      (node (ref "U$1") (pin "16") (pinfunction "TPOUT-_16") (pintype "output"))
    )
    (net (code "110") (name "TX_CONTROLLER") (class "Default")
      (node (ref "PAD3") (pin "1") (pinfunction "P_1") (pintype "passive"))
      (node (ref "R1") (pin "2") (pinfunction "2_2") (pintype "passive"))
      (node (ref "U2") (pin "20") (pinfunction "RXD_20") (pintype "input"))
    )
    (net (code "111") (name "VDD3V3") (class "Default")
      (node (ref "5V_TO_3V3_REGULATOR") (pin "2") (pinfunction "OUT_2") (pintype "passive"))
      (node (ref "5V_TO_3V3_REGULATOR") (pin "4") (pinfunction "OUT_4") (pintype "passive"))
      (node (ref "C10") (pin "1") (pinfunction "1_1") (pintype "passive"))
      (node (ref "C13") (pin "1") (pinfunction "1_1") (pintype "passive"))
      (node (ref "C14") (pin "1") (pinfunction "1_1") (pintype "passive"))
      (node (ref "C27") (pin "1") (pinfunction "1_1") (pintype "passive"))
      (node (ref "C6") (pin "1") (pinfunction "1_1") (pintype "passive"))
      (node (ref "J3") (pin "3") (pinfunction "3_3") (pintype "passive"))
      (node (ref "J5") (pin "4") (pinfunction "4_4") (pintype "passive"))
      (node (ref "L1") (pin "1") (pinfunction "1_1") (pintype "passive"))
      (node (ref "PAD1") (pin "1") (pinfunction "P_1") (pintype "passive"))
      (node (ref "R12") (pin "2") (pinfunction "2_2") (pintype "passive"))
      (node (ref "U$1") (pin "15") (pinfunction "VDDTX_15") (pintype "power_in"))
      (node (ref "U$1") (pin "19") (pinfunction "VDDRX_19") (pintype "power_in"))
      (node (ref "U$1") (pin "20") (pinfunction "VDDPLL_20") (pintype "power_in"))
      (node (ref "U$1") (pin "25") (pinfunction "VDDOSC_25") (pintype "power_in"))
      (node (ref "U$1") (pin "28") (pinfunction "VDD_28") (pintype "power_in"))
      (node (ref "U$2") (pin "VCC") (pinfunction "VCC_VCC") (pintype "bidirectional"))
      (node (ref "U$9") (pin "P$17") (pinfunction "P$17_P$17") (pintype "bidirectional"))
      (node (ref "U$9") (pin "P$18") (pinfunction "P$18_P$18") (pintype "bidirectional"))
      (node (ref "U1") (pin "2") (pinfunction "VDD3V3_2") (pintype "power_in"))
      (node (ref "U4") (pin "4") (pinfunction "VDD_4") (pintype "power_in"))
    )
    (net (code "112") (name "VDD3V3_BRD") (class "Default")
      (node (ref "U$14") (pin "P$19") (pinfunction "P$19_P$19") (pintype "bidirectional"))
      (node (ref "U$14") (pin "P$20") (pinfunction "P$20_P$20") (pintype "bidirectional"))
    )
    (net (code "113") (name "VDD5V") (class "Default")
      (node (ref "5V_TO_3V3_REGULATOR") (pin "3") (pinfunction "IN_3") (pintype "input"))
      (node (ref "C2") (pin "2") (pinfunction "2_2") (pintype "passive"))
      (node (ref "C24") (pin "1") (pinfunction "1_1") (pintype "passive"))
      (node (ref "C25") (pin "1") (pinfunction "1_1") (pintype "passive"))
      (node (ref "C3") (pin "1") (pinfunction "1_1") (pintype "passive"))
      (node (ref "C4") (pin "2") (pinfunction "2_2") (pintype "passive"))
      (node (ref "C5") (pin "1") (pinfunction "1_1") (pintype "passive"))
      (node (ref "C9") (pin "1") (pinfunction "1_1") (pintype "passive"))
      (node (ref "D2") (pin "C") (pinfunction "C_C") (pintype "passive"))
      (node (ref "R2") (pin "2") (pinfunction "2_2") (pintype "passive"))
      (node (ref "SN74HCT245DWR") (pin "1") (pinfunction "DIR_1") (pintype "input"))
      (node (ref "SN74HCT245DWR") (pin "20") (pinfunction "VCC_20") (pintype "power_in"))
      (node (ref "SN74HCT245DWR1") (pin "1") (pinfunction "DIR_1") (pintype "input"))
      (node (ref "SN74HCT245DWR1") (pin "20") (pinfunction "VCC_20") (pintype "power_in"))
      (node (ref "U$9") (pin "P$13") (pinfunction "P$13_P$13") (pintype "bidirectional"))
      (node (ref "U$9") (pin "P$14") (pinfunction "P$14_P$14") (pintype "bidirectional"))
      (node (ref "U4") (pin "3") (pinfunction "VCC_3") (pintype "power_in"))
    )
    (net (code "114") (name "VDD5VUSB") (class "Default")
      (node (ref "D1") (pin "2") (pinfunction "2_2") (pintype "passive"))
      (node (ref "D2") (pin "A") (pinfunction "A_A") (pintype "passive"))
      (node (ref "J2") (pin "A4") (pinfunction "VBUS1_A4") (pintype "passive"))
      (node (ref "J2") (pin "A9") (pinfunction "VBUS2_A9") (pintype "passive"))
      (node (ref "J2") (pin "B4") (pinfunction "VBUS3_B4") (pintype "passive"))
      (node (ref "J2") (pin "B9") (pinfunction "VBUS4_B9") (pintype "passive"))
      (node (ref "U2") (pin "8") (pinfunction "VBUS_8") (pintype "power_in"))
    )
    (net (code "115") (name "VDD5V_BRD") (class "Default")
      (node (ref "C29") (pin "+") (pinfunction "+_+") (pintype "passive"))
      (node (ref "C30") (pin "+") (pinfunction "+_+") (pintype "passive"))
      (node (ref "U$14") (pin "P$23") (pinfunction "P$23_P$23") (pintype "bidirectional"))
      (node (ref "U$14") (pin "P$24") (pinfunction "P$24_P$24") (pintype "bidirectional"))
      (node (ref "U$15") (pin "+") (pinfunction "VCC_+") (pintype "bidirectional"))
      (node (ref "U$15") (pin "+_HOLE") (pinfunction "VCC_HOLE_+_HOLE") (pintype "bidirectional"))
      (node (ref "X13") (pin "1") (pinfunction "K_1") (pintype "passive"))
      (node (ref "X14") (pin "1") (pinfunction "K_1") (pintype "passive"))
      (node (ref "X15") (pin "1") (pinfunction "K_1") (pintype "passive"))
      (node (ref "X16") (pin "1") (pinfunction "K_1") (pintype "passive"))
      (node (ref "X17") (pin "1") (pinfunction "K_1") (pintype "passive"))
      (node (ref "X18") (pin "1") (pinfunction "K_1") (pintype "passive"))
      (node (ref "X19") (pin "1") (pinfunction "K_1") (pintype "passive"))
      (node (ref "X20") (pin "1") (pinfunction "K_1") (pintype "passive"))
      (node (ref "X21") (pin "1") (pinfunction "K_1") (pintype "passive"))
      (node (ref "X22") (pin "1") (pinfunction "K_1") (pintype "passive"))
      (node (ref "X23") (pin "1") (pinfunction "K_1") (pintype "passive"))
      (node (ref "X24") (pin "1") (pinfunction "K_1") (pintype "passive"))
    )
    (net (code "116") (name "VREGIN") (class "Default")
      (node (ref "U2") (pin "7") (pinfunction "VREGIN_7") (pintype "power_in"))
    )
    (net (code "117") (name "unconnected-(J1-RING1_SWITCH-Pad11)") (class "Default")
      (node (ref "J1") (pin "11") (pinfunction "RING1_SWITCH_11") (pintype "passive"))
    )
    (net (code "118") (name "unconnected-(J1-TIP_SWITCH-Pad10)") (class "Default")
      (node (ref "J1") (pin "10") (pinfunction "TIP_SWITCH_10") (pintype "passive"))
    )
    (net (code "119") (name "unconnected-(J2-CC1-PadA5)") (class "Default")
      (node (ref "J2") (pin "A5") (pinfunction "CC1_A5") (pintype "passive"))
    )
    (net (code "120") (name "unconnected-(J2-CC2-PadB5)") (class "Default")
      (node (ref "J2") (pin "B5") (pinfunction "CC2_B5") (pintype "passive"))
    )
    (net (code "121") (name "unconnected-(J2-RX1+-PadB11)") (class "Default")
      (node (ref "J2") (pin "B11") (pinfunction "RX1+_B11") (pintype "passive"))
    )
    (net (code "122") (name "unconnected-(J2-RX1--PadB10)") (class "Default")
      (node (ref "J2") (pin "B10") (pinfunction "RX1-_B10") (pintype "passive"))
    )
    (net (code "123") (name "unconnected-(J2-RX2+-PadA11)") (class "Default")
      (node (ref "J2") (pin "A11") (pinfunction "RX2+_A11") (pintype "passive"))
    )
    (net (code "124") (name "unconnected-(J2-RX2--PadA10)") (class "Default")
      (node (ref "J2") (pin "A10") (pinfunction "RX2-_A10") (pintype "passive"))
    )
    (net (code "125") (name "unconnected-(J2-SBU1-PadA8)") (class "Default")
      (node (ref "J2") (pin "A8") (pinfunction "SBU1_A8") (pintype "passive"))
    )
    (net (code "126") (name "unconnected-(J2-SBU2-PadB8)") (class "Default")
      (node (ref "J2") (pin "B8") (pinfunction "SBU2_B8") (pintype "passive"))
    )
    (net (code "127") (name "unconnected-(J2-TX1+-PadA2)") (class "Default")
      (node (ref "J2") (pin "A2") (pinfunction "TX1+_A2") (pintype "passive"))
    )
    (net (code "128") (name "unconnected-(J2-TX1--PadA3)") (class "Default")
      (node (ref "J2") (pin "A3") (pinfunction "TX1-_A3") (pintype "passive"))
    )
    (net (code "129") (name "unconnected-(J2-TX2+-PadB2)") (class "Default")
      (node (ref "J2") (pin "B2") (pinfunction "TX2+_B2") (pintype "passive"))
    )
    (net (code "130") (name "unconnected-(J2-TX2--PadB3)") (class "Default")
      (node (ref "J2") (pin "B3") (pinfunction "TX2-_B3") (pintype "passive"))
    )
    (net (code "131") (name "unconnected-(P1-PadR4)") (class "Default")
      (node (ref "P1") (pin "R4") (pinfunction "R4_R4") (pintype "input"))
    )
    (net (code "132") (name "unconnected-(P1-PadR5)") (class "Default")
      (node (ref "P1") (pin "R5") (pinfunction "R5_R5") (pintype "input"))
    )
    (net (code "133") (name "unconnected-(P1-PadR6)") (class "Default")
      (node (ref "P1") (pin "R6") (pinfunction "R6_R6") (pintype "input"))
    )
    (net (code "134") (name "unconnected-(SN74HCT245DWR-A3-Pad4)") (class "Default")
      (node (ref "SN74HCT245DWR") (pin "4") (pinfunction "A3_4") (pintype "bidirectional"))
    )
    (net (code "135") (name "unconnected-(SN74HCT245DWR-B3-Pad16)") (class "Default")
      (node (ref "SN74HCT245DWR") (pin "16") (pinfunction "B3_16") (pintype "bidirectional"))
    )
    (net (code "136") (name "unconnected-(SN74HCT245DWR1-A3-Pad4)") (class "Default")
      (node (ref "SN74HCT245DWR1") (pin "4") (pinfunction "A3_4") (pintype "bidirectional"))
    )
    (net (code "137") (name "unconnected-(SN74HCT245DWR1-A6-Pad7)") (class "Default")
      (node (ref "SN74HCT245DWR1") (pin "7") (pinfunction "A6_7") (pintype "bidirectional"))
    )
    (net (code "138") (name "unconnected-(SN74HCT245DWR1-A8-Pad9)") (class "Default")
      (node (ref "SN74HCT245DWR1") (pin "9") (pinfunction "A8_9") (pintype "bidirectional"))
    )
    (net (code "139") (name "unconnected-(SN74HCT245DWR1-B3-Pad16)") (class "Default")
      (node (ref "SN74HCT245DWR1") (pin "16") (pinfunction "B3_16") (pintype "bidirectional"))
    )
    (net (code "140") (name "unconnected-(SN74HCT245DWR1-B6-Pad13)") (class "Default")
      (node (ref "SN74HCT245DWR1") (pin "13") (pinfunction "B6_13") (pintype "bidirectional"))
    )
    (net (code "141") (name "unconnected-(SN74HCT245DWR1-B8-Pad11)") (class "Default")
      (node (ref "SN74HCT245DWR1") (pin "11") (pinfunction "B8_11") (pintype "bidirectional"))
    )
    (net (code "142") (name "unconnected-(U$1-CLKOUT-Pad3)") (class "Default")
      (node (ref "U$1") (pin "3") (pinfunction "CLKOUT_3") (pintype "output"))
    )
    (net (code "143") (name "unconnected-(U$1-NC-Pad5)") (class "Default")
      (node (ref "U$1") (pin "5") (pinfunction "NC_5") (pintype "no_connect"))
    )
    (net (code "144") (name "unconnected-(U$2-PadESD1)") (class "Default")
      (node (ref "U$2") (pin "ESD1") (pinfunction "ESD1_ESD1") (pintype "bidirectional"))
    )
    (net (code "145") (name "unconnected-(U$2-PadESD2)") (class "Default")
      (node (ref "U$2") (pin "ESD2") (pinfunction "ESD2_ESD2") (pintype "bidirectional"))
    )
    (net (code "146") (name "unconnected-(U$2-PadESD3)") (class "Default")
      (node (ref "U$2") (pin "ESD3") (pinfunction "ESD3_ESD3") (pintype "bidirectional"))
    )
    (net (code "147") (name "unconnected-(U$2-PadGND)") (class "Default")
      (node (ref "U$2") (pin "GND") (pinfunction "GND_GND") (pintype "bidirectional"))
    )
    (net (code "148") (name "unconnected-(U$2-PadSDDATA1)") (class "Default")
      (node (ref "U$2") (pin "SDDATA1") (pinfunction "SDDATA1_SDDATA1") (pintype "bidirectional"))
    )
    (net (code "149") (name "unconnected-(U$2-PadSDDATA2)") (class "Default")
      (node (ref "U$2") (pin "SDDATA2") (pinfunction "SDDATA2_SDDATA2") (pintype "bidirectional"))
    )
    (net (code "150") (name "unconnected-(U1-SCK{slash}CLK-Pad20)") (class "Default")
      (node (ref "U1") (pin "20") (pinfunction "SCK/CLK_20") (pintype "bidirectional"))
    )
    (net (code "151") (name "unconnected-(U1-SCS{slash}CMD-Pad19)") (class "Default")
      (node (ref "U1") (pin "19") (pinfunction "SCS/CMD_19") (pintype "bidirectional"))
    )
    (net (code "152") (name "unconnected-(U1-SDI{slash}SD1-Pad22)") (class "Default")
      (node (ref "U1") (pin "22") (pinfunction "SDI/SD1_22") (pintype "bidirectional"))
    )
    (net (code "153") (name "unconnected-(U1-SDO{slash}SD0-Pad21)") (class "Default")
      (node (ref "U1") (pin "21") (pinfunction "SDO/SD0_21") (pintype "bidirectional"))
    )
    (net (code "154") (name "unconnected-(U1-SHD{slash}SD2-Pad17)") (class "Default")
      (node (ref "U1") (pin "17") (pinfunction "SHD/SD2_17") (pintype "bidirectional"))
    )
    (net (code "155") (name "unconnected-(U1-SWP{slash}SD3-Pad18)") (class "Default")
      (node (ref "U1") (pin "18") (pinfunction "SWP/SD3_18") (pintype "bidirectional"))
    )
    (net (code "156") (name "unconnected-(U2-CTS-Pad18)") (class "Default")
      (node (ref "U2") (pin "18") (pinfunction "CTS_18") (pintype "input"))
    )
    (net (code "157") (name "unconnected-(U2-DCD-Pad24)") (class "Default")
      (node (ref "U2") (pin "24") (pinfunction "DCD_24") (pintype "bidirectional"))
    )
    (net (code "158") (name "unconnected-(U2-DSR-Pad22)") (class "Default")
      (node (ref "U2") (pin "22") (pinfunction "DSR_22") (pintype "bidirectional"))
    )
    (net (code "159") (name "unconnected-(U2-GPIO.0{slash}TXT-Pad14)") (class "Default")
      (node (ref "U2") (pin "14") (pinfunction "GPIO.0/TXT_14") (pintype "bidirectional"))
    )
    (net (code "160") (name "unconnected-(U2-GPIO.1{slash}RXT-Pad13)") (class "Default")
      (node (ref "U2") (pin "13") (pinfunction "GPIO.1/RXT_13") (pintype "bidirectional"))
    )
    (net (code "161") (name "unconnected-(U2-GPIO.2{slash}RS485-Pad12)") (class "Default")
      (node (ref "U2") (pin "12") (pinfunction "GPIO.2/RS485_12") (pintype "bidirectional"))
    )
    (net (code "162") (name "unconnected-(U2-GPIO.3{slash}WAKEUP-Pad11)") (class "Default")
      (node (ref "U2") (pin "11") (pinfunction "GPIO.3/WAKEUP_11") (pintype "bidirectional"))
    )
    (net (code "163") (name "unconnected-(U2-RI{slash}CLK-Pad1)") (class "Default")
      (node (ref "U2") (pin "1") (pinfunction "RI/CLK_1") (pintype "input"))
    )
    (net (code "164") (name "unconnected-(U2-SUSPEND-Pad17)") (class "Default")
      (node (ref "U2") (pin "17") (pinfunction "SUSPEND_17") (pintype "output"))
    )
    (net (code "165") (name "unconnected-(U2-VIO-Pad5)") (class "Default")
      (node (ref "U2") (pin "5") (pinfunction "VIO_5") (pintype "bidirectional"))
    )
    (net (code "166") (name "unconnected-(U2-~{SUSPEND}-Pad15)") (class "Default")
      (node (ref "U2") (pin "15") (pinfunction "~{SUSPEND}_15") (pintype "output"))
    )
  )
)
